# SuperCapV3Control.net
KiCad netlist of a schematic drawn in Altium Designer
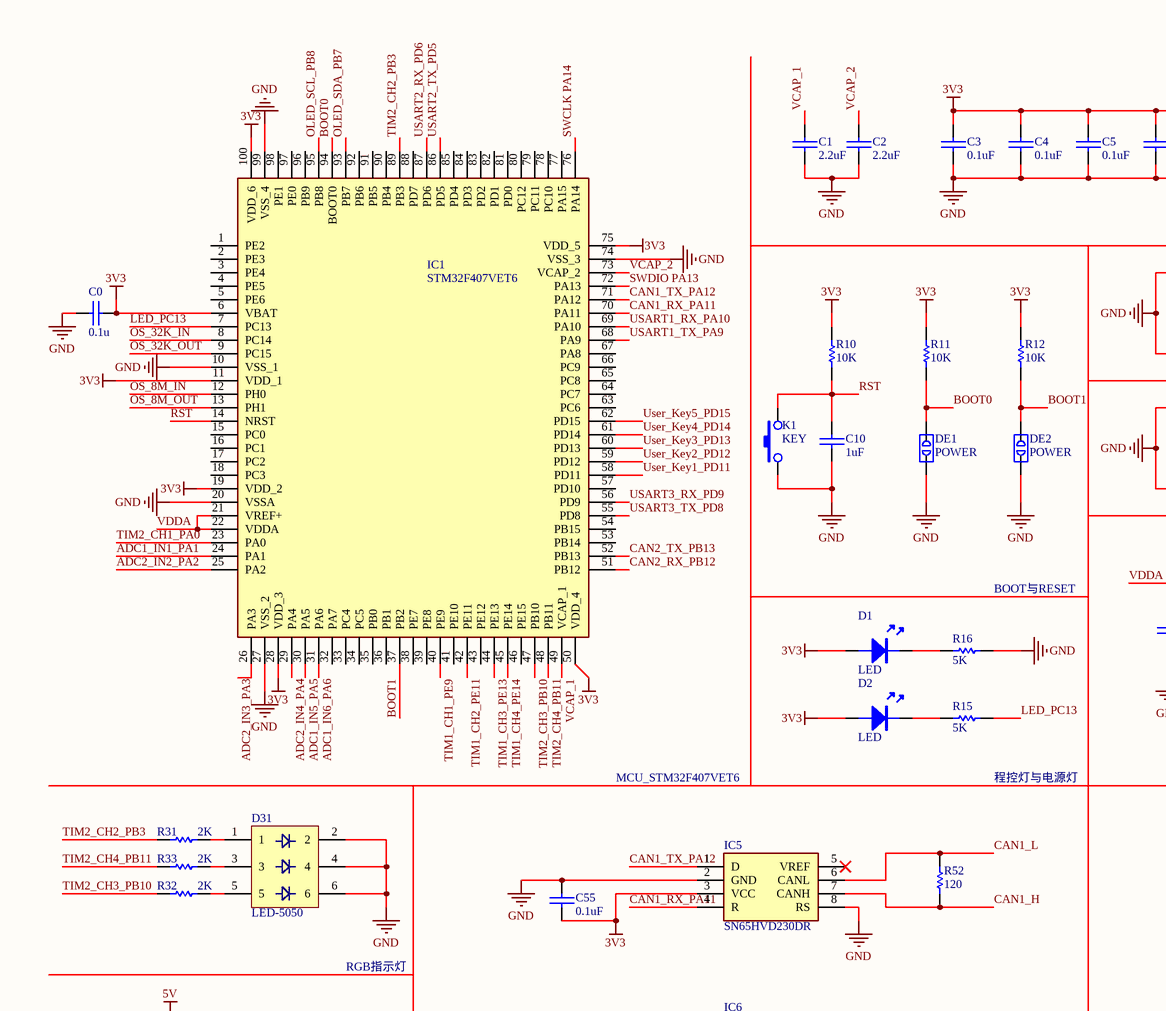
[diagram p0: SuperCapV3Control.SchDoc, top left]
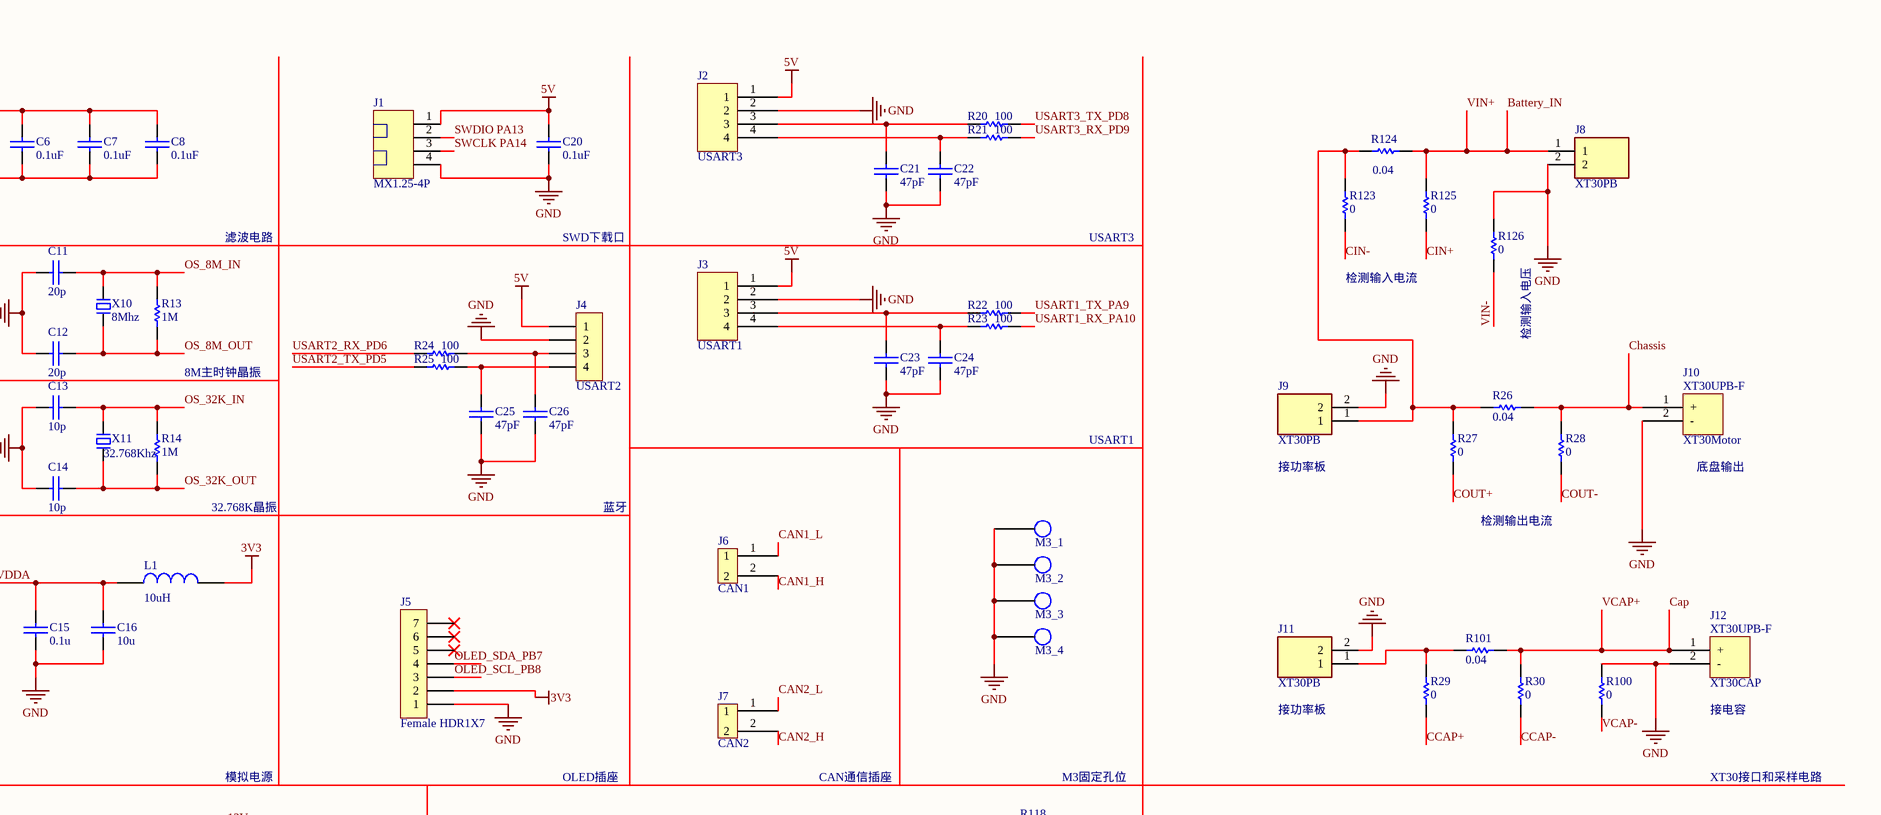
[diagram p1: SuperCapV3Control.SchDoc, top right]
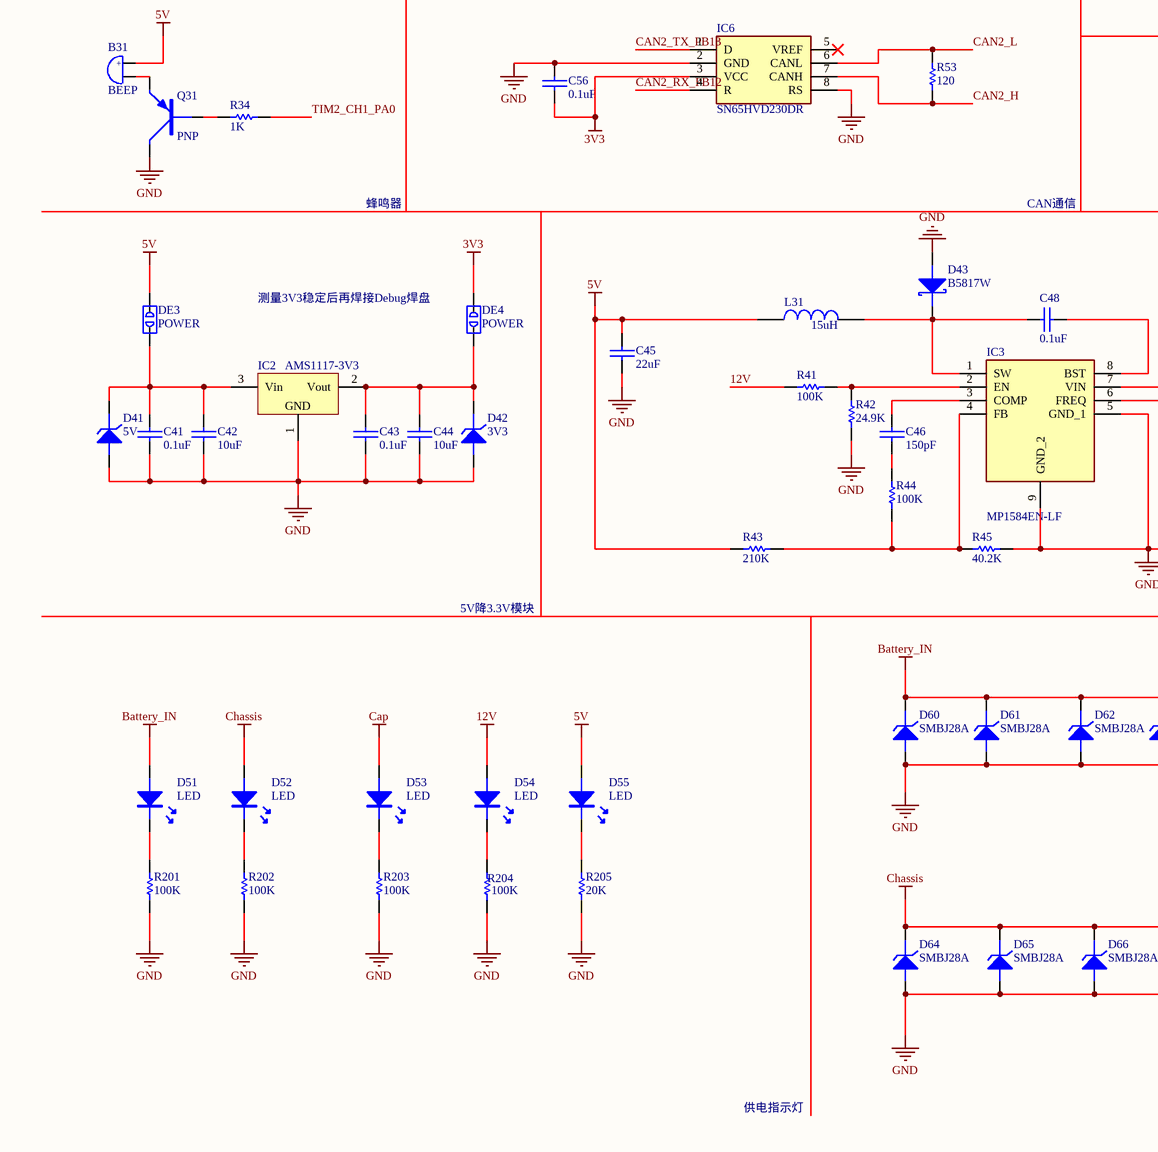
[diagram p2: SuperCapV3Control.SchDoc, bottom left]
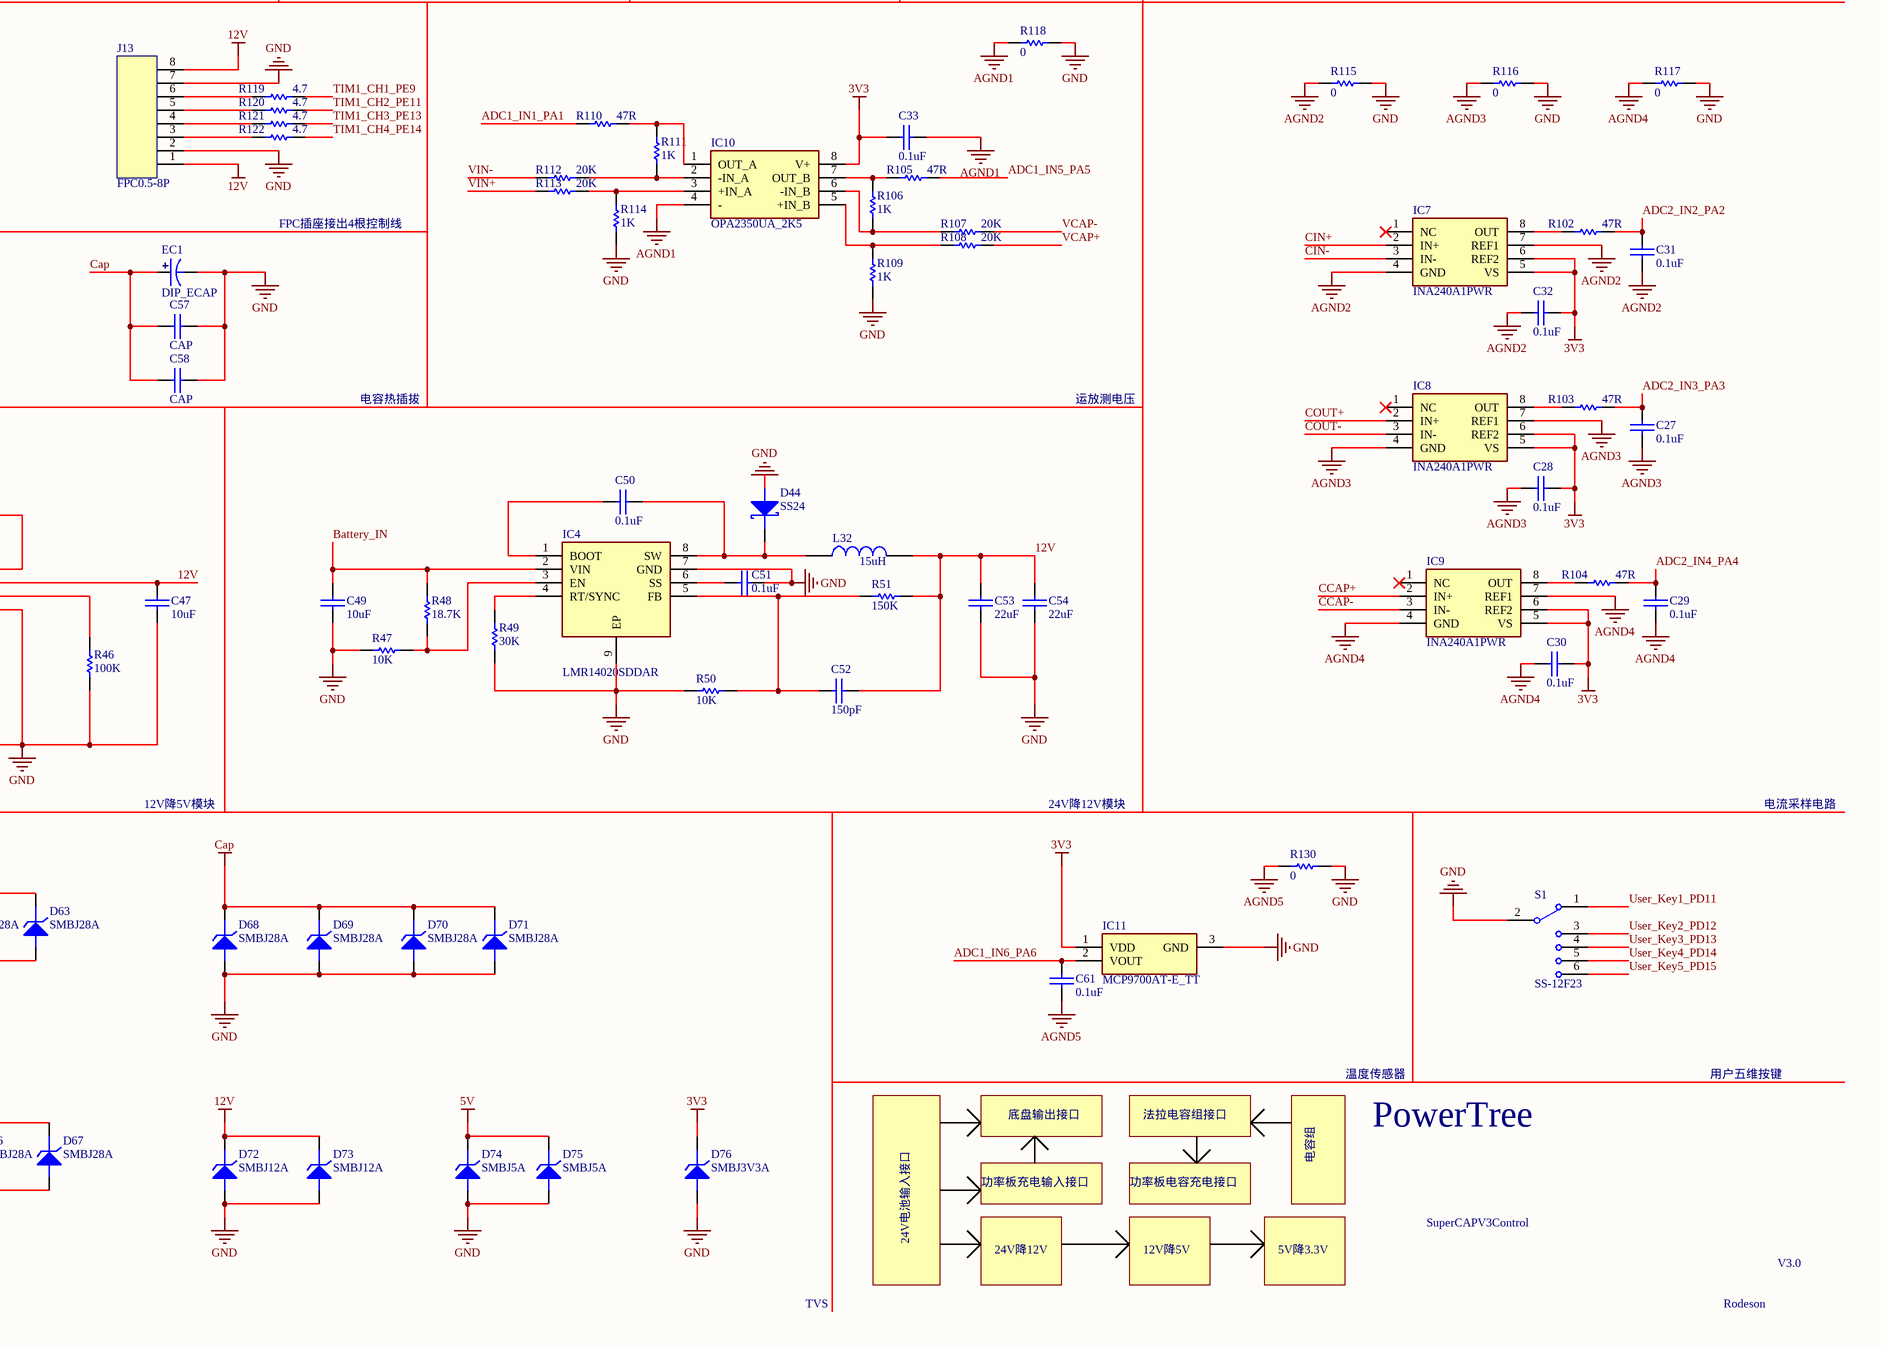
[diagram p3: SuperCapV3Control.SchDoc, bottom right]

(export (version "E")
  (design (tool "Eeschema 10.0.6"))
  (components
    (comp (ref "B31")
      (value "BEEP")
      (footprint "BEEP 6.5x12x8.5")
      (description "蜂鸣器")
      (libsource (lib "蜂鸣器") (part "BEEP"))
    )
    (comp (ref "C0")
      (value "0.1u")
      (footprint "0603C")
      (description "无极性电容")
      (libsource (lib "电容") (part "CAP"))
    )
    (comp (ref "C1")
      (value "2.2uF")
      (footprint "0603C")
      (description "无极性电容")
      (libsource (lib "电容") (part "CAP"))
    )
    (comp (ref "C2")
      (value "2.2uF")
      (footprint "0603C")
      (description "无极性电容")
      (libsource (lib "电容") (part "CAP"))
    )
    (comp (ref "C3")
      (value "0.1uF")
      (footprint "0603C")
      (description "无极性电容")
      (libsource (lib "电容") (part "CAP"))
    )
    (comp (ref "C4")
      (value "0.1uF")
      (footprint "0603C")
      (description "无极性电容")
      (libsource (lib "电容") (part "CAP"))
    )
    (comp (ref "C5")
      (value "0.1uF")
      (footprint "0603C")
      (description "无极性电容")
      (libsource (lib "电容") (part "CAP"))
    )
    (comp (ref "C6")
      (value "0.1uF")
      (footprint "0603C")
      (description "无极性电容")
      (libsource (lib "电容") (part "CAP"))
    )
    (comp (ref "C7")
      (value "0.1uF")
      (footprint "0603C")
      (description "无极性电容")
      (libsource (lib "电容") (part "CAP"))
    )
    (comp (ref "C8")
      (value "0.1uF")
      (footprint "0603C")
      (description "无极性电容")
      (libsource (lib "电容") (part "CAP"))
    )
    (comp (ref "C10")
      (value "1uF")
      (footprint "0603C")
      (description "无极性电容")
      (libsource (lib "电容") (part "CAP"))
    )
    (comp (ref "C11")
      (value "20p")
      (footprint "0603C")
      (description "无极性电容")
      (libsource (lib "电容") (part "CAP"))
    )
    (comp (ref "C12")
      (value "20p")
      (footprint "0603C")
      (description "无极性电容")
      (libsource (lib "电容") (part "CAP"))
    )
    (comp (ref "C13")
      (value "10p")
      (footprint "0603C")
      (description "无极性电容")
      (libsource (lib "电容") (part "CAP"))
    )
    (comp (ref "C14")
      (value "10p")
      (footprint "0603C")
      (description "无极性电容")
      (libsource (lib "电容") (part "CAP"))
    )
    (comp (ref "C15")
      (value "0.1u")
      (footprint "0603C")
      (description "无极性电容")
      (libsource (lib "电容") (part "CAP"))
    )
    (comp (ref "C16")
      (value "10u")
      (footprint "0603C")
      (description "无极性电容")
      (libsource (lib "电容") (part "CAP"))
    )
    (comp (ref "C20")
      (value "0.1uF")
      (footprint "0603C")
      (description "无极性电容")
      (libsource (lib "电容") (part "CAP"))
    )
    (comp (ref "C21")
      (value "47pF")
      (footprint "0603C")
      (description "无极性电容")
      (libsource (lib "电容") (part "CAP"))
    )
    (comp (ref "C22")
      (value "47pF")
      (footprint "0603C")
      (description "无极性电容")
      (libsource (lib "电容") (part "CAP"))
    )
    (comp (ref "C23")
      (value "47pF")
      (footprint "0603C")
      (description "无极性电容")
      (libsource (lib "电容") (part "CAP"))
    )
    (comp (ref "C24")
      (value "47pF")
      (footprint "0603C")
      (description "无极性电容")
      (libsource (lib "电容") (part "CAP"))
    )
    (comp (ref "C25")
      (value "47pF")
      (footprint "0603C")
      (description "无极性电容")
      (libsource (lib "电容") (part "CAP"))
    )
    (comp (ref "C26")
      (value "47pF")
      (footprint "0603C")
      (description "无极性电容")
      (libsource (lib "电容") (part "CAP"))
    )
    (comp (ref "C27")
      (value "0.1uF")
      (footprint "0603C")
      (description "无极性电容")
      (libsource (lib "电容") (part "CAP"))
    )
    (comp (ref "C28")
      (value "0.1uF")
      (footprint "0603C")
      (description "无极性电容")
      (libsource (lib "电容") (part "CAP"))
    )
    (comp (ref "C29")
      (value "0.1uF")
      (footprint "0603C")
      (description "无极性电容")
      (libsource (lib "电容") (part "CAP"))
    )
    (comp (ref "C30")
      (value "0.1uF")
      (footprint "0603C")
      (description "无极性电容")
      (libsource (lib "电容") (part "CAP"))
    )
    (comp (ref "C31")
      (value "0.1uF")
      (footprint "0603C")
      (description "无极性电容")
      (libsource (lib "电容") (part "CAP"))
    )
    (comp (ref "C32")
      (value "0.1uF")
      (footprint "0603C")
      (description "无极性电容")
      (libsource (lib "电容") (part "CAP"))
    )
    (comp (ref "C33")
      (value "0.1uF")
      (footprint "0603C")
      (description "无极性电容")
      (libsource (lib "电容") (part "CAP"))
    )
    (comp (ref "C41")
      (value "0.1uF")
      (footprint "0805C")
      (description "无极性电容")
      (libsource (lib "电容") (part "CAP"))
    )
    (comp (ref "C42")
      (value "10uF")
      (footprint "0805C")
      (description "无极性电容")
      (libsource (lib "电容") (part "CAP"))
    )
    (comp (ref "C43")
      (value "0.1uF")
      (footprint "0805C")
      (description "无极性电容")
      (libsource (lib "电容") (part "CAP"))
    )
    (comp (ref "C44")
      (value "10uF")
      (footprint "0805C")
      (description "无极性电容")
      (libsource (lib "电容") (part "CAP"))
    )
    (comp (ref "C45")
      (value "22uF")
      (footprint "1206C")
      (description "无极性电容")
      (libsource (lib "电容") (part "CAP"))
    )
    (comp (ref "C46")
      (value "150pF")
      (footprint "0603C")
      (description "无极性电容")
      (libsource (lib "电容") (part "CAP"))
    )
    (comp (ref "C47")
      (value "10uF")
      (footprint "1206C")
      (description "无极性电容")
      (libsource (lib "电容") (part "CAP"))
    )
    (comp (ref "C48")
      (value "0.1uF")
      (footprint "0603C")
      (description "无极性电容")
      (libsource (lib "电容") (part "CAP"))
    )
    (comp (ref "C49")
      (value "10uF")
      (footprint "1206C")
      (description "无极性电容")
      (libsource (lib "电容") (part "CAP"))
    )
    (comp (ref "C50")
      (value "0.1uF")
      (footprint "0603C")
      (description "无极性电容")
      (libsource (lib "电容") (part "CAP"))
    )
    (comp (ref "C51")
      (value "0.1uF")
      (footprint "0603C")
      (description "无极性电容")
      (libsource (lib "电容") (part "CAP"))
    )
    (comp (ref "C52")
      (value "150pF")
      (footprint "0603C")
      (description "无极性电容")
      (libsource (lib "电容") (part "CAP"))
    )
    (comp (ref "C53")
      (value "22uF")
      (footprint "1206C")
      (description "无极性电容")
      (libsource (lib "电容") (part "CAP"))
    )
    (comp (ref "C54")
      (value "22uF")
      (footprint "1206C")
      (description "无极性电容")
      (libsource (lib "电容") (part "CAP"))
    )
    (comp (ref "C55")
      (value "0.1uF")
      (footprint "0603C")
      (description "无极性电容")
      (libsource (lib "电容") (part "CAP"))
    )
    (comp (ref "C56")
      (value "0.1uF")
      (footprint "0603C")
      (description "无极性电容")
      (libsource (lib "电容") (part "CAP"))
    )
    (comp (ref "C57")
      (value "CAP")
      (footprint "1812C")
      (description "无极性电容")
      (libsource (lib "电容") (part "CAP"))
    )
    (comp (ref "C58")
      (value "CAP")
      (footprint "1812C")
      (description "无极性电容")
      (libsource (lib "电容") (part "CAP"))
    )
    (comp (ref "C61")
      (value "0.1uF")
      (footprint "0603C")
      (description "无极性电容")
      (libsource (lib "电容") (part "CAP"))
    )
    (comp (ref "D1") (value "LED") (footprint "LED-0603G") (libsource (lib "LED") (part "LED")))
    (comp (ref "D2") (value "LED") (footprint "LED-0603G") (libsource (lib "LED") (part "LED")))
    (comp (ref "D31") (value "LED-5050") (footprint "LED-5050W") (libsource (lib "LED") (part "LED-5050")))
    (comp (ref "D41")
      (value "5V")
      (footprint "SMC/DO-214AB")
      (description "稳压二极管")
      (libsource (lib "二极管") (part "DIODE ZENER"))
    )
    (comp (ref "D42")
      (value "3V3")
      (footprint "SMC/DO-214AB")
      (description "稳压二极管")
      (libsource (lib "二极管") (part "DIODE ZENER"))
    )
    (comp (ref "D43")
      (value "B5817W")
      (footprint "SMA/DO-214AC")
      (description "肖特基二极管")
      (libsource (lib "SuperCap_V2") (part "DIODE SCHOTTKY"))
    )
    (comp (ref "D44")
      (value "SS24")
      (footprint "SMA/DO-214AC")
      (description "肖特基二极管")
      (libsource (lib "SuperCap_V2") (part "DIODE SCHOTTKY"))
    )
    (comp (ref "D51") (value "LED") (footprint "LED-0603G") (libsource (lib "5VDC") (part "LED")))
    (comp (ref "D52") (value "LED") (footprint "LED-0603G") (libsource (lib "5VDC") (part "LED")))
    (comp (ref "D53") (value "LED") (footprint "LED-0603G") (libsource (lib "5VDC") (part "LED")))
    (comp (ref "D54") (value "LED") (footprint "LED-0603G") (libsource (lib "5VDC") (part "LED")))
    (comp (ref "D55") (value "LED") (footprint "LED-0603G") (libsource (lib "5VDC") (part "LED")))
    (comp (ref "D60")
      (value "SMBJ28A")
      (footprint "SMB/DO-214AA")
      (description "稳压二极管")
      (libsource (lib "二极管") (part "DIODE ZENER"))
    )
    (comp (ref "D61")
      (value "SMBJ28A")
      (footprint "SMB/DO-214AA")
      (description "稳压二极管")
      (libsource (lib "二极管") (part "DIODE ZENER"))
    )
    (comp (ref "D62")
      (value "SMBJ28A")
      (footprint "SMB/DO-214AA")
      (description "稳压二极管")
      (libsource (lib "二极管") (part "DIODE ZENER"))
    )
    (comp (ref "D63")
      (value "SMBJ28A")
      (footprint "SMB/DO-214AA")
      (description "稳压二极管")
      (libsource (lib "二极管") (part "DIODE ZENER"))
    )
    (comp (ref "D64")
      (value "SMBJ28A")
      (footprint "SMB/DO-214AA")
      (description "稳压二极管")
      (libsource (lib "二极管") (part "DIODE ZENER"))
    )
    (comp (ref "D65")
      (value "SMBJ28A")
      (footprint "SMB/DO-214AA")
      (description "稳压二极管")
      (libsource (lib "二极管") (part "DIODE ZENER"))
    )
    (comp (ref "D66")
      (value "SMBJ28A")
      (footprint "SMB/DO-214AA")
      (description "稳压二极管")
      (libsource (lib "二极管") (part "DIODE ZENER"))
    )
    (comp (ref "D67")
      (value "SMBJ28A")
      (footprint "SMB/DO-214AA")
      (description "稳压二极管")
      (libsource (lib "二极管") (part "DIODE ZENER"))
    )
    (comp (ref "D68")
      (value "SMBJ28A")
      (footprint "SMB/DO-214AA")
      (description "稳压二极管")
      (libsource (lib "二极管") (part "DIODE ZENER"))
    )
    (comp (ref "D69")
      (value "SMBJ28A")
      (footprint "SMB/DO-214AA")
      (description "稳压二极管")
      (libsource (lib "二极管") (part "DIODE ZENER"))
    )
    (comp (ref "D70")
      (value "SMBJ28A")
      (footprint "SMB/DO-214AA")
      (description "稳压二极管")
      (libsource (lib "二极管") (part "DIODE ZENER"))
    )
    (comp (ref "D71")
      (value "SMBJ28A")
      (footprint "SMB/DO-214AA")
      (description "稳压二极管")
      (libsource (lib "二极管") (part "DIODE ZENER"))
    )
    (comp (ref "D72")
      (value "SMBJ12A")
      (footprint "SMB/DO-214AA")
      (description "稳压二极管")
      (libsource (lib "二极管") (part "DIODE ZENER"))
    )
    (comp (ref "D73")
      (value "SMBJ12A")
      (footprint "SMB/DO-214AA")
      (description "稳压二极管")
      (libsource (lib "二极管") (part "DIODE ZENER"))
    )
    (comp (ref "D74")
      (value "SMBJ5A")
      (footprint "SMB/DO-214AA")
      (description "稳压二极管")
      (libsource (lib "二极管") (part "DIODE ZENER"))
    )
    (comp (ref "D75")
      (value "SMBJ5A")
      (footprint "SMB/DO-214AA")
      (description "稳压二极管")
      (libsource (lib "二极管") (part "DIODE ZENER"))
    )
    (comp (ref "D76")
      (value "SMBJ3V3A")
      (footprint "SMB/DO-214AA")
      (description "稳压二极管")
      (libsource (lib "二极管") (part "DIODE ZENER"))
    )
    (comp (ref "DE1")
      (value "POWER")
      (footprint "DEBUG_A")
      (description "调试断点焊盘")
      (fields (field (name "版权归属") "源创客"))
      (libsource (lib "装甲板第二版") (part "DEBUG"))
    )
    (comp (ref "DE2")
      (value "POWER")
      (footprint "DEBUG_A")
      (description "调试断点焊盘")
      (fields (field (name "版权归属") "源创客"))
      (libsource (lib "装甲板第二版") (part "DEBUG"))
    )
    (comp (ref "DE3")
      (value "POWER")
      (footprint "DEBUG_A")
      (description "调试断点焊盘")
      (fields (field (name "版权归属") "源创客"))
      (libsource (lib "装甲板第二版") (part "DEBUG"))
    )
    (comp (ref "DE4")
      (value "POWER")
      (footprint "DEBUG_A")
      (description "调试断点焊盘")
      (fields (field (name "版权归属") "源创客"))
      (libsource (lib "装甲板第二版") (part "DEBUG"))
    )
    (comp (ref "EC1")
      (value "DIP_ECAP")
      (footprint "DIP-EC5.0X10X20-A")
      (description "直插电解电容")
      (libsource (lib "电容") (part "DIP_ECAP"))
    )
    (comp (ref "IC1")
      (value "STM32F407VET6")
      (footprint "SamacSys:QFP50P1600X1600X160-100N")
      (description "Integrated Circuit")
      (fields (field (name "MOUSER PART NUMBER") "511-STM32F407VET6"))
      (libsource (lib "*") (part "STM32F407VET6"))
    )
    (comp (ref "IC2")
      (value "AMS1117-3V3")
      (footprint "SOT-223")
      (description "三端稳压芯片")
      (fields (field (name "版权归属") "源创客"))
      (libsource (lib "装甲板第二版") (part "AMS1117"))
    )
    (comp (ref "IC3")
      (value "MP1584EN-LF")
      (footprint "SamacSys:SOIC127P600X170-9N")
      (description "Integrated Circuit")
      (fields (field (name "MOUSER PART NUMBER") "946-MP1584ENLF"))
      (libsource (lib "SamacSys") (part "MP1584EN-LF"))
    )
    (comp (ref "IC4")
      (value "LMR14020SDDAR")
      (footprint "SamacSys:SOIC127P600X170-9N")
      (description "Integrated Circuit")
      (fields (field (name "MOUSER PART NUMBER") "595-LMR14020SDDAR"))
      (libsource (lib "*") (part "LMR14020SDDAR"))
    )
    (comp (ref "IC5")
      (value "SN65HVD230DR")
      (footprint "SamacSys:SOT127P600X175-8N")
      (description "Integrated Circuit")
      (fields (field (name "MOUSER PART NUMBER") "595-SN65HVD230DR"))
      (libsource (lib "*") (part "SN65HVD230DR"))
    )
    (comp (ref "IC6")
      (value "SN65HVD230DR")
      (footprint "SamacSys:SOT127P600X175-8N")
      (description "Integrated Circuit")
      (fields (field (name "MOUSER PART NUMBER") "595-SN65HVD230DR"))
      (libsource (lib "*") (part "SN65HVD230DR"))
    )
    (comp (ref "IC7")
      (value "INA240A1PWR")
      (footprint "SamacSys:SOP65P640X120-8N")
      (description "Integrated Circuit")
      (fields (field (name "MOUSER PART NUMBER") "595-INA240A1PWR"))
      (libsource (lib "*") (part "INA240A1PWR"))
    )
    (comp (ref "IC8")
      (value "INA240A1PWR")
      (footprint "SamacSys:SOP65P640X120-8N")
      (description "Integrated Circuit")
      (fields (field (name "MOUSER PART NUMBER") "595-INA240A1PWR"))
      (libsource (lib "*") (part "INA240A1PWR"))
    )
    (comp (ref "IC9")
      (value "INA240A1PWR")
      (footprint "SamacSys:SOP65P640X120-8N")
      (description "Integrated Circuit")
      (fields (field (name "MOUSER PART NUMBER") "595-INA240A1PWR"))
      (libsource (lib "*") (part "INA240A1PWR"))
    )
    (comp (ref "IC10")
      (value "OPA2350UA_2K5")
      (footprint "SamacSys:SOIC127P600X175-8N")
      (description "Integrated Circuit")
      (fields
        (field (name "MANUFACTURER_PART_NUMBER") "OPA2350UA/2K5")
        (field (name "MOUSER PART NUMBER") "595-OPA2350UA/2K5")
      )
      (libsource (lib "*") (part "OPA2350UA_2K5"))
    )
    (comp (ref "IC11")
      (value "MCP9700AT-E_TT")
      (footprint "SOT23")
      (description "Integrated Circuit")
      (fields
        (field (name "MANUFACTURER_PART_NUMBER") "MCP9700AT-E/TT")
        (field (name "MOUSER PART NUMBER") "579-MCP9700AT-E/TT")
      )
      (libsource (lib "*") (part "MCP9700AT-E_TT"))
    )
    (comp (ref "J1") (value "MX1.25-4P") (footprint "MX1.25WS-4P") (libsource (lib "MX") (part "MX1.25-4P")))
    (comp (ref "J2") (value "USART3") (footprint "GH1.25_4P") (libsource (lib "GH1.25") (part "GH1.25_4P")))
    (comp (ref "J3") (value "USART1") (footprint "GH1.25_4P") (libsource (lib "GH1.25") (part "GH1.25_4P")))
    (comp (ref "J4")
      (value "USART2")
      (footprint "Fe-HDR1X4/2.54-S")
      (libsource (lib "排母") (part "Female HDR1X4"))
    )
    (comp (ref "J5")
      (value "Female HDR1X7")
      (footprint "Fe-HDR1X7/2.54-S")
      (libsource (lib "排母") (part "Female HDR1X7"))
    )
    (comp (ref "J6") (value "CAN1") (footprint "GH1.25_2P") (libsource (lib "GH1.25") (part "GH1.25_2P")))
    (comp (ref "J7") (value "CAN2") (footprint "GH1.25_2P") (libsource (lib "GH1.25") (part "GH1.25_2P")))
    (comp (ref "J8")
      (value "XT30PB")
      (footprint "SamacSys:XT30PB")
      (description "Connector")
      (libsource (lib "SamacSys") (part "XT30PB"))
    )
    (comp (ref "J9")
      (value "XT30PB")
      (footprint "SamacSys:XT30PB")
      (description "Connector")
      (libsource (lib "") (part "XT30PB_1"))
    )
    (comp (ref "J10")
      (value "XT30Motor")
      (footprint "XT30UPB-F")
      (libsource (lib "powerdesigner") (part "XT30UPB-F"))
    )
    (comp (ref "J11")
      (value "XT30PB")
      (footprint "SamacSys:XT30PB")
      (description "Connector")
      (libsource (lib "") (part "XT30PB_1"))
    )
    (comp (ref "J12")
      (value "XT30CAP")
      (footprint "XT30UPB-F")
      (libsource (lib "powerdesigner") (part "XT30UPB-F"))
    )
    (comp (ref "J13")
      (value "FPC0.5-8P")
      (footprint "FPC0.5-8P")
      (description "贴片")
      (libsource (lib "FPC") (part "FPC0.5-8P"))
    )
    (comp (ref "K1") (value "KEY") (footprint "SMD-3X6X2.5") (libsource (lib "轻触开关") (part "KEY")))
    (comp (ref "L1")
      (value "10uH")
      (footprint "0603L")
      (description "INDUCTOR")
      (libsource (lib "电感") (part "INDUCTOR"))
    )
    (comp (ref "L31")
      (value "15uH")
      (footprint "0630L")
      (description "INDUCTOR")
      (libsource (lib "电感") (part "INDUCTOR"))
    )
    (comp (ref "L32")
      (value "15uH")
      (footprint "0630L")
      (description "INDUCTOR")
      (libsource (lib "电感") (part "INDUCTOR"))
    )
    (comp (ref "M3_1") (value "Hole") (footprint "M3") (libsource (lib "SuperCap_V2") (part "Hole")))
    (comp (ref "M3_2") (value "Hole") (footprint "M3") (libsource (lib "SuperCap_V2") (part "Hole")))
    (comp (ref "M3_3") (value "Hole") (footprint "M3") (libsource (lib "SuperCap_V2") (part "Hole")))
    (comp (ref "M3_4") (value "Hole") (footprint "M3") (libsource (lib "SuperCap_V2") (part "Hole")))
    (comp (ref "Q31")
      (value "PNP")
      (footprint "SOT-23")
      (description "PNP三极管")
      (libsource (lib "三极管") (part "PNP"))
    )
    (comp (ref "R10") (value "10K") (footprint "0603R") (libsource (lib "电阻") (part "RES")))
    (comp (ref "R11") (value "10K") (footprint "0603R") (libsource (lib "电阻") (part "RES")))
    (comp (ref "R12") (value "10K") (footprint "0603R") (libsource (lib "电阻") (part "RES")))
    (comp (ref "R13") (value "1M") (footprint "0805R") (libsource (lib "电阻") (part "RES")))
    (comp (ref "R14") (value "1M") (footprint "0805R") (libsource (lib "电阻") (part "RES")))
    (comp (ref "R15") (value "5K") (footprint "0603R") (libsource (lib "电阻") (part "RES")))
    (comp (ref "R16") (value "5K") (footprint "0603R") (libsource (lib "电阻") (part "RES")))
    (comp (ref "R20") (value "100") (footprint "0603R") (libsource (lib "电阻") (part "RES")))
    (comp (ref "R21") (value "100") (footprint "0603R") (libsource (lib "电阻") (part "RES")))
    (comp (ref "R22") (value "100") (footprint "0603R") (libsource (lib "电阻") (part "RES")))
    (comp (ref "R23") (value "100") (footprint "0603R") (libsource (lib "电阻") (part "RES")))
    (comp (ref "R24") (value "100") (footprint "0603R") (libsource (lib "电阻") (part "RES")))
    (comp (ref "R25") (value "100") (footprint "0603R") (libsource (lib "电阻") (part "RES")))
    (comp (ref "R26") (value "0.04") (footprint "2512R") (libsource (lib "电阻") (part "RES")))
    (comp (ref "R27") (value "0") (footprint "0603R") (libsource (lib "电阻") (part "RES")))
    (comp (ref "R28") (value "0") (footprint "0603R") (libsource (lib "电阻") (part "RES")))
    (comp (ref "R29") (value "0") (footprint "0603R") (libsource (lib "电阻") (part "RES")))
    (comp (ref "R30") (value "0") (footprint "0603R") (libsource (lib "电阻") (part "RES")))
    (comp (ref "R31") (value "2K") (footprint "0603R") (libsource (lib "电阻") (part "RES")))
    (comp (ref "R32") (value "2K") (footprint "0603R") (libsource (lib "电阻") (part "RES")))
    (comp (ref "R33") (value "2K") (footprint "0603R") (libsource (lib "电阻") (part "RES")))
    (comp (ref "R34") (value "1K") (footprint "0603R") (libsource (lib "电阻") (part "RES")))
    (comp (ref "R41") (value "100K") (footprint "0603R") (libsource (lib "电阻") (part "RES")))
    (comp (ref "R42") (value "24.9K") (footprint "0603R") (libsource (lib "电阻") (part "RES")))
    (comp (ref "R43") (value "210K") (footprint "0603R") (libsource (lib "电阻") (part "RES")))
    (comp (ref "R44") (value "100K") (footprint "0603R") (libsource (lib "电阻") (part "RES")))
    (comp (ref "R45") (value "40.2K") (footprint "0603R") (libsource (lib "电阻") (part "RES")))
    (comp (ref "R46") (value "100K") (footprint "0603R") (libsource (lib "电阻") (part "RES")))
    (comp (ref "R47") (value "10K") (footprint "0603R") (libsource (lib "电阻") (part "RES")))
    (comp (ref "R48") (value "18.7K") (footprint "0603R") (libsource (lib "电阻") (part "RES")))
    (comp (ref "R49") (value "30K") (footprint "0603R") (libsource (lib "电阻") (part "RES")))
    (comp (ref "R50") (value "10K") (footprint "0603R") (libsource (lib "电阻") (part "RES")))
    (comp (ref "R51") (value "150K") (footprint "0603R") (libsource (lib "电阻") (part "RES")))
    (comp (ref "R52") (value "120") (footprint "0603R") (libsource (lib "电阻") (part "RES")))
    (comp (ref "R53") (value "120") (footprint "0603R") (libsource (lib "电阻") (part "RES")))
    (comp (ref "R100") (value "0") (footprint "0603R") (libsource (lib "电阻") (part "RES")))
    (comp (ref "R101") (value "0.04") (footprint "2512R") (libsource (lib "电阻") (part "RES")))
    (comp (ref "R102") (value "47R") (footprint "0805R") (libsource (lib "电阻") (part "RES")))
    (comp (ref "R103") (value "47R") (footprint "0805R") (libsource (lib "电阻") (part "RES")))
    (comp (ref "R104") (value "47R") (footprint "0805R") (libsource (lib "电阻") (part "RES")))
    (comp (ref "R105") (value "47R") (footprint "0603R") (libsource (lib "电阻") (part "RES")))
    (comp (ref "R106") (value "1K") (footprint "0603R") (libsource (lib "电阻") (part "RES")))
    (comp (ref "R107") (value "20K") (footprint "0603R") (libsource (lib "电阻") (part "RES")))
    (comp (ref "R108") (value "20K") (footprint "0603R") (libsource (lib "电阻") (part "RES")))
    (comp (ref "R109") (value "1K") (footprint "0603R") (libsource (lib "电阻") (part "RES")))
    (comp (ref "R110") (value "47R") (footprint "0603R") (libsource (lib "电阻") (part "RES")))
    (comp (ref "R111") (value "1K") (footprint "0603R") (libsource (lib "电阻") (part "RES")))
    (comp (ref "R112") (value "20K") (footprint "0603R") (libsource (lib "电阻") (part "RES")))
    (comp (ref "R113") (value "20K") (footprint "0603R") (libsource (lib "电阻") (part "RES")))
    (comp (ref "R114") (value "1K") (footprint "0603R") (libsource (lib "电阻") (part "RES")))
    (comp (ref "R115") (value "0") (footprint "0603R") (libsource (lib "电阻") (part "RES")))
    (comp (ref "R116") (value "0") (footprint "0603R") (libsource (lib "电阻") (part "RES")))
    (comp (ref "R117") (value "0") (footprint "0603R") (libsource (lib "电阻") (part "RES")))
    (comp (ref "R118") (value "0") (footprint "0603R") (libsource (lib "电阻") (part "RES")))
    (comp (ref "R119") (value "4.7") (footprint "0603R") (libsource (lib "电阻") (part "RES")))
    (comp (ref "R120") (value "4.7") (footprint "0603R") (libsource (lib "电阻") (part "RES")))
    (comp (ref "R121") (value "4.7") (footprint "0603R") (libsource (lib "电阻") (part "RES")))
    (comp (ref "R122") (value "4.7") (footprint "0603R") (libsource (lib "电阻") (part "RES")))
    (comp (ref "R123") (value "0") (footprint "0603R") (libsource (lib "电阻") (part "RES")))
    (comp (ref "R124") (value "0.04") (footprint "2512R") (libsource (lib "电阻") (part "RES")))
    (comp (ref "R125") (value "0") (footprint "0603R") (libsource (lib "电阻") (part "RES")))
    (comp (ref "R126") (value "0") (footprint "0603R") (libsource (lib "电阻") (part "RES")))
    (comp (ref "R130") (value "0") (footprint "0603R") (libsource (lib "电阻") (part "RES")))
    (comp (ref "R201") (value "100K") (footprint "0603R") (libsource (lib "电阻") (part "RES")))
    (comp (ref "R202") (value "100K") (footprint "0603R") (libsource (lib "电阻") (part "RES")))
    (comp (ref "R203") (value "100K") (footprint "0603R") (libsource (lib "电阻") (part "RES")))
    (comp (ref "R204") (value "100K") (footprint "0603R") (libsource (lib "电阻") (part "RES")))
    (comp (ref "R205") (value "20K") (footprint "0603R") (libsource (lib "电阻") (part "RES")))
    (comp (ref "S1")
      (value "SS-12F23")
      (footprint "五向开关")
      (description "五向开关")
      (fields (field (name "版权归属") "源创客"))
      (libsource (lib "试做1型") (part "SSW-1P"))
    )
    (comp (ref "X10")
      (value "8Mhz")
      (footprint "OSC HC-49S")
      (description "2脚无源脚晶振")
      (libsource (lib "晶振") (part "XTAL-2P"))
    )
    (comp (ref "X11")
      (value "32.768Khz")
      (footprint "OSC HC-49S")
      (description "2脚无源脚晶振")
      (libsource (lib "晶振") (part "XTAL-2P"))
    )
  )
  (nets
    (net (code "1") (name "/ADC1_IN1_PA1") (class "Default")
      (node (ref "IC1") (pin "24") (pinfunction "PA1_24") (pintype "passive"))
      (node (ref "R110") (pin "1") (pinfunction "1_1") (pintype "passive"))
    )
    (net (code "2") (name "/ADC1_IN5_PA5") (class "Default")
      (node (ref "IC1") (pin "30") (pinfunction "PA5_30") (pintype "passive"))
      (node (ref "R105") (pin "2") (pinfunction "2_2") (pintype "passive"))
    )
    (net (code "3") (name "/ADC1_IN6_PA6") (class "Default")
      (node (ref "C61") (pin "2") (pinfunction "2_2") (pintype "passive"))
      (node (ref "IC1") (pin "31") (pinfunction "PA6_31") (pintype "passive"))
      (node (ref "IC11") (pin "2") (pinfunction "VOUT_2") (pintype "passive"))
    )
    (net (code "4") (name "/ADC2_IN2_PA2") (class "Default")
      (node (ref "C31") (pin "1") (pinfunction "1_1") (pintype "passive"))
      (node (ref "IC1") (pin "25") (pinfunction "PA2_25") (pintype "passive"))
      (node (ref "R102") (pin "2") (pinfunction "2_2") (pintype "passive"))
    )
    (net (code "5") (name "/ADC2_IN3_PA3") (class "Default")
      (node (ref "C27") (pin "1") (pinfunction "1_1") (pintype "passive"))
      (node (ref "IC1") (pin "26") (pinfunction "PA3_26") (pintype "passive"))
      (node (ref "R103") (pin "2") (pinfunction "2_2") (pintype "passive"))
    )
    (net (code "6") (name "/ADC2_IN4_PA4") (class "Default")
      (node (ref "C29") (pin "1") (pinfunction "1_1") (pintype "passive"))
      (node (ref "IC1") (pin "29") (pinfunction "PA4_29") (pintype "passive"))
      (node (ref "R104") (pin "2") (pinfunction "2_2") (pintype "passive"))
    )
    (net (code "7") (name "/BOOT0") (class "Default")
      (node (ref "DE1") (pin "2") (pinfunction "2_2") (pintype "passive"))
      (node (ref "IC1") (pin "94") (pinfunction "BOOT0_94") (pintype "passive"))
      (node (ref "R11") (pin "1") (pinfunction "1_1") (pintype "passive"))
    )
    (net (code "8") (name "/BOOT1") (class "Default")
      (node (ref "DE2") (pin "2") (pinfunction "2_2") (pintype "passive"))
      (node (ref "IC1") (pin "37") (pinfunction "PB2_37") (pintype "passive"))
      (node (ref "R12") (pin "1") (pinfunction "1_1") (pintype "passive"))
    )
    (net (code "9") (name "/CAN1_H") (class "Default")
      (node (ref "IC5") (pin "7") (pinfunction "CANH_7") (pintype "passive"))
      (node (ref "J6") (pin "2") (pinfunction "2_2") (pintype "passive"))
      (node (ref "R52") (pin "1") (pinfunction "1_1") (pintype "passive"))
    )
    (net (code "10") (name "/CAN1_L") (class "Default")
      (node (ref "IC5") (pin "6") (pinfunction "CANL_6") (pintype "passive"))
      (node (ref "J6") (pin "1") (pinfunction "1_1") (pintype "passive"))
      (node (ref "R52") (pin "2") (pinfunction "2_2") (pintype "passive"))
    )
    (net (code "11") (name "/CAN1_RX_PA11") (class "Default")
      (node (ref "IC1") (pin "70") (pinfunction "PA11_70") (pintype "passive"))
      (node (ref "IC5") (pin "4") (pinfunction "R_4") (pintype "passive"))
    )
    (net (code "12") (name "/CAN1_TX_PA12") (class "Default")
      (node (ref "IC1") (pin "71") (pinfunction "PA12_71") (pintype "passive"))
      (node (ref "IC5") (pin "1") (pinfunction "D_1") (pintype "passive"))
    )
    (net (code "13") (name "/CAN2_H") (class "Default")
      (node (ref "IC6") (pin "7") (pinfunction "CANH_7") (pintype "passive"))
      (node (ref "J7") (pin "2") (pinfunction "2_2") (pintype "passive"))
      (node (ref "R53") (pin "1") (pinfunction "1_1") (pintype "passive"))
    )
    (net (code "14") (name "/CAN2_L") (class "Default")
      (node (ref "IC6") (pin "6") (pinfunction "CANL_6") (pintype "passive"))
      (node (ref "J7") (pin "1") (pinfunction "1_1") (pintype "passive"))
      (node (ref "R53") (pin "2") (pinfunction "2_2") (pintype "passive"))
    )
    (net (code "15") (name "/CAN2_RX_PB12") (class "Default")
      (node (ref "IC1") (pin "51") (pinfunction "PB12_51") (pintype "passive"))
      (node (ref "IC6") (pin "4") (pinfunction "R_4") (pintype "passive"))
    )
    (net (code "16") (name "/CAN2_TX_PB13") (class "Default")
      (node (ref "IC1") (pin "52") (pinfunction "PB13_52") (pintype "passive"))
      (node (ref "IC6") (pin "1") (pinfunction "D_1") (pintype "passive"))
    )
    (net (code "17") (name "/CCAP+") (class "Default")
      (node (ref "IC9") (pin "2") (pinfunction "IN+_2") (pintype "passive"))
      (node (ref "R29") (pin "1") (pinfunction "1_1") (pintype "passive"))
    )
    (net (code "18") (name "/CCAP-") (class "Default")
      (node (ref "IC9") (pin "3") (pinfunction "IN-_3") (pintype "passive"))
      (node (ref "R30") (pin "1") (pinfunction "1_1") (pintype "passive"))
    )
    (net (code "19") (name "/CIN+") (class "Default")
      (node (ref "IC7") (pin "2") (pinfunction "IN+_2") (pintype "passive"))
      (node (ref "R125") (pin "1") (pinfunction "1_1") (pintype "passive"))
    )
    (net (code "20") (name "/CIN-") (class "Default")
      (node (ref "IC7") (pin "3") (pinfunction "IN-_3") (pintype "passive"))
      (node (ref "R123") (pin "1") (pinfunction "1_1") (pintype "passive"))
    )
    (net (code "21") (name "/COUT+") (class "Default")
      (node (ref "IC8") (pin "2") (pinfunction "IN+_2") (pintype "passive"))
      (node (ref "R27") (pin "1") (pinfunction "1_1") (pintype "passive"))
    )
    (net (code "22") (name "/COUT-") (class "Default")
      (node (ref "IC8") (pin "3") (pinfunction "IN-_3") (pintype "passive"))
      (node (ref "R28") (pin "1") (pinfunction "1_1") (pintype "passive"))
    )
    (net (code "23") (name "/LED_PC13") (class "Default")
      (node (ref "IC1") (pin "7") (pinfunction "PC13_7") (pintype "passive"))
      (node (ref "R15") (pin "2") (pinfunction "2_2") (pintype "passive"))
    )
    (net (code "24") (name "/OLED_SCL_PB8") (class "Default")
      (node (ref "IC1") (pin "95") (pinfunction "PB8_95") (pintype "passive"))
      (node (ref "J5") (pin "3") (pinfunction "3_3") (pintype "passive"))
    )
    (net (code "25") (name "/OLED_SDA_PB7") (class "Default")
      (node (ref "IC1") (pin "93") (pinfunction "PB7_93") (pintype "passive"))
      (node (ref "J5") (pin "4") (pinfunction "4_4") (pintype "passive"))
    )
    (net (code "26") (name "/OS_8M_IN") (class "Default")
      (node (ref "C11") (pin "2") (pinfunction "2_2") (pintype "passive"))
      (node (ref "IC1") (pin "12") (pinfunction "PH0_12") (pintype "passive"))
      (node (ref "R13") (pin "2") (pinfunction "2_2") (pintype "passive"))
      (node (ref "X10") (pin "2") (pinfunction "2_2") (pintype "passive"))
    )
    (net (code "27") (name "/OS_8M_OUT") (class "Default")
      (node (ref "C12") (pin "2") (pinfunction "2_2") (pintype "passive"))
      (node (ref "IC1") (pin "13") (pinfunction "PH1_13") (pintype "passive"))
      (node (ref "R13") (pin "1") (pinfunction "1_1") (pintype "passive"))
      (node (ref "X10") (pin "1") (pinfunction "1_1") (pintype "passive"))
    )
    (net (code "28") (name "/OS_32K_IN") (class "Default")
      (node (ref "C13") (pin "2") (pinfunction "2_2") (pintype "passive"))
      (node (ref "IC1") (pin "8") (pinfunction "PC14_8") (pintype "passive"))
      (node (ref "R14") (pin "2") (pinfunction "2_2") (pintype "passive"))
      (node (ref "X11") (pin "2") (pinfunction "2_2") (pintype "passive"))
    )
    (net (code "29") (name "/OS_32K_OUT") (class "Default")
      (node (ref "C14") (pin "2") (pinfunction "2_2") (pintype "passive"))
      (node (ref "IC1") (pin "9") (pinfunction "PC15_9") (pintype "passive"))
      (node (ref "R14") (pin "1") (pinfunction "1_1") (pintype "passive"))
      (node (ref "X11") (pin "1") (pinfunction "1_1") (pintype "passive"))
    )
    (net (code "30") (name "/RST") (class "Default")
      (node (ref "C10") (pin "2") (pinfunction "2_2") (pintype "passive"))
      (node (ref "IC1") (pin "14") (pinfunction "NRST_14") (pintype "passive"))
      (node (ref "K1") (pin "3") (pinfunction "3_3") (pintype "passive"))
      (node (ref "R10") (pin "1") (pinfunction "1_1") (pintype "passive"))
    )
    (net (code "31") (name "/SWCLK PA14") (class "Default")
      (node (ref "IC1") (pin "76") (pinfunction "PA14_76") (pintype "passive"))
      (node (ref "J1") (pin "3") (pinfunction "3_3") (pintype "passive"))
    )
    (net (code "32") (name "/SWDIO PA13") (class "Default")
      (node (ref "IC1") (pin "72") (pinfunction "PA13_72") (pintype "passive"))
      (node (ref "J1") (pin "2") (pinfunction "2_2") (pintype "passive"))
    )
    (net (code "33") (name "/TIM1_CH1_PE9") (class "Default")
      (node (ref "IC1") (pin "40") (pinfunction "PE9_40") (pintype "passive"))
      (node (ref "R119") (pin "2") (pinfunction "2_2") (pintype "passive"))
    )
    (net (code "34") (name "/TIM1_CH2_PE11") (class "Default")
      (node (ref "IC1") (pin "42") (pinfunction "PE11_42") (pintype "passive"))
      (node (ref "R120") (pin "2") (pinfunction "2_2") (pintype "passive"))
    )
    (net (code "35") (name "/TIM1_CH3_PE13") (class "Default")
      (node (ref "IC1") (pin "44") (pinfunction "PE13_44") (pintype "passive"))
      (node (ref "R121") (pin "2") (pinfunction "2_2") (pintype "passive"))
    )
    (net (code "36") (name "/TIM1_CH4_PE14") (class "Default")
      (node (ref "IC1") (pin "45") (pinfunction "PE14_45") (pintype "passive"))
      (node (ref "R122") (pin "2") (pinfunction "2_2") (pintype "passive"))
    )
    (net (code "37") (name "/TIM2_CH1_PA0") (class "Default")
      (node (ref "IC1") (pin "23") (pinfunction "PA0_23") (pintype "passive"))
      (node (ref "R34") (pin "2") (pinfunction "2_2") (pintype "passive"))
    )
    (net (code "38") (name "/TIM2_CH2_PB3") (class "Default")
      (node (ref "IC1") (pin "89") (pinfunction "PB3_89") (pintype "passive"))
      (node (ref "R31") (pin "1") (pinfunction "1_1") (pintype "passive"))
    )
    (net (code "39") (name "/TIM2_CH3_PB10") (class "Default")
      (node (ref "IC1") (pin "47") (pinfunction "PB10_47") (pintype "passive"))
      (node (ref "R32") (pin "1") (pinfunction "1_1") (pintype "passive"))
    )
    (net (code "40") (name "/TIM2_CH4_PB11") (class "Default")
      (node (ref "IC1") (pin "48") (pinfunction "PB11_48") (pintype "passive"))
      (node (ref "R33") (pin "1") (pinfunction "1_1") (pintype "passive"))
    )
    (net (code "41") (name "/USART1_RX_PA10") (class "Default")
      (node (ref "IC1") (pin "69") (pinfunction "PA10_69") (pintype "passive"))
      (node (ref "R23") (pin "2") (pinfunction "2_2") (pintype "passive"))
    )
    (net (code "42") (name "/USART1_TX_PA9") (class "Default")
      (node (ref "IC1") (pin "68") (pinfunction "PA9_68") (pintype "passive"))
      (node (ref "R22") (pin "2") (pinfunction "2_2") (pintype "passive"))
    )
    (net (code "43") (name "/USART2_RX_PD6") (class "Default")
      (node (ref "IC1") (pin "87") (pinfunction "PD6_87") (pintype "passive"))
      (node (ref "R24") (pin "1") (pinfunction "1_1") (pintype "passive"))
    )
    (net (code "44") (name "/USART2_TX_PD5") (class "Default")
      (node (ref "IC1") (pin "86") (pinfunction "PD5_86") (pintype "passive"))
      (node (ref "R25") (pin "1") (pinfunction "1_1") (pintype "passive"))
    )
    (net (code "45") (name "/USART3_RX_PD9") (class "Default")
      (node (ref "IC1") (pin "56") (pinfunction "PD9_56") (pintype "passive"))
      (node (ref "R21") (pin "2") (pinfunction "2_2") (pintype "passive"))
    )
    (net (code "46") (name "/USART3_TX_PD8") (class "Default")
      (node (ref "IC1") (pin "55") (pinfunction "PD8_55") (pintype "passive"))
      (node (ref "R20") (pin "2") (pinfunction "2_2") (pintype "passive"))
    )
    (net (code "47") (name "/User_Key1_PD11") (class "Default")
      (node (ref "IC1") (pin "58") (pinfunction "PD11_58") (pintype "passive"))
      (node (ref "S1") (pin "1") (pinfunction "1_1") (pintype "passive"))
    )
    (net (code "48") (name "/User_Key2_PD12") (class "Default")
      (node (ref "IC1") (pin "59") (pinfunction "PD12_59") (pintype "passive"))
      (node (ref "S1") (pin "3") (pinfunction "3_3") (pintype "passive"))
    )
    (net (code "49") (name "/User_Key3_PD13") (class "Default")
      (node (ref "IC1") (pin "60") (pinfunction "PD13_60") (pintype "passive"))
      (node (ref "S1") (pin "4") (pinfunction "4_4") (pintype "passive"))
    )
    (net (code "50") (name "/User_Key4_PD14") (class "Default")
      (node (ref "IC1") (pin "61") (pinfunction "PD14_61") (pintype "passive"))
      (node (ref "S1") (pin "5") (pinfunction "5_5") (pintype "passive"))
    )
    (net (code "51") (name "/User_Key5_PD15") (class "Default")
      (node (ref "IC1") (pin "62") (pinfunction "PD15_62") (pintype "passive"))
      (node (ref "S1") (pin "6") (pinfunction "6_6") (pintype "passive"))
    )
    (net (code "52") (name "/VCAP-") (class "Default")
      (node (ref "R100") (pin "1") (pinfunction "1_1") (pintype "passive"))
      (node (ref "R107") (pin "2") (pinfunction "2_2") (pintype "passive"))
    )
    (net (code "53") (name "/VCAP_1") (class "Default")
      (node (ref "C1") (pin "2") (pinfunction "2_2") (pintype "passive"))
      (node (ref "IC1") (pin "49") (pinfunction "VCAP_1_49") (pintype "passive"))
    )
    (net (code "54") (name "/VCAP_2") (class "Default")
      (node (ref "C2") (pin "2") (pinfunction "2_2") (pintype "passive"))
      (node (ref "IC1") (pin "73") (pinfunction "VCAP_2_73") (pintype "passive"))
    )
    (net (code "55") (name "/VDDA") (class "Default")
      (node (ref "C15") (pin "2") (pinfunction "2_2") (pintype "passive"))
      (node (ref "C16") (pin "2") (pinfunction "2_2") (pintype "passive"))
      (node (ref "IC1") (pin "21") (pinfunction "VREF+_21") (pintype "passive"))
      (node (ref "IC1") (pin "22") (pinfunction "VDDA_22") (pintype "passive"))
      (node (ref "L1") (pin "1") (pinfunction "1_1") (pintype "passive"))
    )
    (net (code "56") (name "/VIN-") (class "Default")
      (node (ref "R112") (pin "1") (pinfunction "1_1") (pintype "passive"))
      (node (ref "R126") (pin "1") (pinfunction "1_1") (pintype "passive"))
    )
    (net (code "57") (name "3V3") (class "Default")
      (node (ref "C0") (pin "1") (pinfunction "1_1") (pintype "passive"))
      (node (ref "C28") (pin "2") (pinfunction "2_2") (pintype "passive"))
      (node (ref "C3") (pin "2") (pinfunction "2_2") (pintype "passive"))
      (node (ref "C30") (pin "2") (pinfunction "2_2") (pintype "passive"))
      (node (ref "C32") (pin "2") (pinfunction "2_2") (pintype "passive"))
      (node (ref "C33") (pin "1") (pinfunction "1_1") (pintype "passive"))
      (node (ref "C4") (pin "2") (pinfunction "2_2") (pintype "passive"))
      (node (ref "C5") (pin "2") (pinfunction "2_2") (pintype "passive"))
      (node (ref "C55") (pin "1") (pinfunction "1_1") (pintype "passive"))
      (node (ref "C56") (pin "1") (pinfunction "1_1") (pintype "passive"))
      (node (ref "C6") (pin "2") (pinfunction "2_2") (pintype "passive"))
      (node (ref "C7") (pin "2") (pinfunction "2_2") (pintype "passive"))
      (node (ref "C8") (pin "2") (pinfunction "2_2") (pintype "passive"))
      (node (ref "D1") (pin "A") (pinfunction "A_A") (pintype "passive"))
      (node (ref "D2") (pin "A") (pinfunction "A_A") (pintype "passive"))
      (node (ref "D76") (pin "K") (pinfunction "K_K") (pintype "passive"))
      (node (ref "DE4") (pin "1") (pinfunction "1_1") (pintype "passive"))
      (node (ref "IC1") (pin "100") (pinfunction "VDD_6_100") (pintype "passive"))
      (node (ref "IC1") (pin "11") (pinfunction "VDD_1_11") (pintype "passive"))
      (node (ref "IC1") (pin "19") (pinfunction "VDD_2_19") (pintype "passive"))
      (node (ref "IC1") (pin "28") (pinfunction "VDD_3_28") (pintype "passive"))
      (node (ref "IC1") (pin "50") (pinfunction "VDD_4_50") (pintype "passive"))
      (node (ref "IC1") (pin "6") (pinfunction "VBAT_6") (pintype "passive"))
      (node (ref "IC1") (pin "75") (pinfunction "VDD_5_75") (pintype "passive"))
      (node (ref "IC10") (pin "8") (pinfunction "V+_8") (pintype "passive"))
      (node (ref "IC11") (pin "1") (pinfunction "VDD_1") (pintype "passive"))
      (node (ref "IC5") (pin "3") (pinfunction "VCC_3") (pintype "passive"))
      (node (ref "IC6") (pin "3") (pinfunction "VCC_3") (pintype "passive"))
      (node (ref "IC7") (pin "5") (pinfunction "VS_5") (pintype "passive"))
      (node (ref "IC7") (pin "6") (pinfunction "REF2_6") (pintype "passive"))
      (node (ref "IC8") (pin "5") (pinfunction "VS_5") (pintype "passive"))
      (node (ref "IC8") (pin "6") (pinfunction "REF2_6") (pintype "passive"))
      (node (ref "IC9") (pin "5") (pinfunction "VS_5") (pintype "passive"))
      (node (ref "IC9") (pin "6") (pinfunction "REF2_6") (pintype "passive"))
      (node (ref "J5") (pin "2") (pinfunction "2_2") (pintype "passive"))
      (node (ref "L1") (pin "2") (pinfunction "2_2") (pintype "passive"))
      (node (ref "R10") (pin "2") (pinfunction "2_2") (pintype "passive"))
      (node (ref "R11") (pin "2") (pinfunction "2_2") (pintype "passive"))
      (node (ref "R12") (pin "2") (pinfunction "2_2") (pintype "passive"))
    )
    (net (code "58") (name "5V") (class "Default")
      (node (ref "B31") (pin "1") (pinfunction "1_1") (pintype "passive"))
      (node (ref "C20") (pin "2") (pinfunction "2_2") (pintype "passive"))
      (node (ref "C45") (pin "2") (pinfunction "2_2") (pintype "passive"))
      (node (ref "D55") (pin "A") (pinfunction "A_A") (pintype "passive"))
      (node (ref "D74") (pin "K") (pinfunction "K_K") (pintype "passive"))
      (node (ref "D75") (pin "K") (pinfunction "K_K") (pintype "passive"))
      (node (ref "DE3") (pin "1") (pinfunction "1_1") (pintype "passive"))
      (node (ref "J1") (pin "1") (pinfunction "1_1") (pintype "passive"))
      (node (ref "J2") (pin "1") (pinfunction "1_1") (pintype "passive"))
      (node (ref "J3") (pin "1") (pinfunction "1_1") (pintype "passive"))
      (node (ref "J4") (pin "1") (pinfunction "1_1") (pintype "passive"))
      (node (ref "L31") (pin "1") (pinfunction "1_1") (pintype "passive"))
      (node (ref "R43") (pin "1") (pinfunction "1_1") (pintype "passive"))
    )
    (net (code "59") (name "12V") (class "Default")
      (node (ref "C47") (pin "2") (pinfunction "2_2") (pintype "passive"))
      (node (ref "C52") (pin "2") (pinfunction "2_2") (pintype "passive"))
      (node (ref "C53") (pin "2") (pinfunction "2_2") (pintype "passive"))
      (node (ref "C54") (pin "2") (pinfunction "2_2") (pintype "passive"))
      (node (ref "D54") (pin "A") (pinfunction "A_A") (pintype "passive"))
      (node (ref "D72") (pin "K") (pinfunction "K_K") (pintype "passive"))
      (node (ref "D73") (pin "K") (pinfunction "K_K") (pintype "passive"))
      (node (ref "IC3") (pin "7") (pinfunction "VIN_7") (pintype "passive"))
      (node (ref "J13") (pin "1") (pinfunction "1_1") (pintype "passive"))
      (node (ref "J13") (pin "8") (pinfunction "8_8") (pintype "passive"))
      (node (ref "L32") (pin "2") (pinfunction "2_2") (pintype "passive"))
      (node (ref "R41") (pin "1") (pinfunction "1_1") (pintype "passive"))
      (node (ref "R51") (pin "2") (pinfunction "2_2") (pintype "passive"))
    )
    (net (code "60") (name "AGND1") (class "Default")
      (node (ref "C33") (pin "2") (pinfunction "2_2") (pintype "passive"))
      (node (ref "IC10") (pin "4") (pinfunction "-_4") (pintype "passive"))
      (node (ref "R118") (pin "2") (pinfunction "2_2") (pintype "passive"))
    )
    (net (code "61") (name "AGND2") (class "Default")
      (node (ref "C31") (pin "2") (pinfunction "2_2") (pintype "passive"))
      (node (ref "C32") (pin "1") (pinfunction "1_1") (pintype "passive"))
      (node (ref "IC7") (pin "4") (pinfunction "GND_4") (pintype "passive"))
      (node (ref "IC7") (pin "7") (pinfunction "REF1_7") (pintype "passive"))
      (node (ref "R115") (pin "2") (pinfunction "2_2") (pintype "passive"))
    )
    (net (code "62") (name "AGND3") (class "Default")
      (node (ref "C27") (pin "2") (pinfunction "2_2") (pintype "passive"))
      (node (ref "C28") (pin "1") (pinfunction "1_1") (pintype "passive"))
      (node (ref "IC8") (pin "4") (pinfunction "GND_4") (pintype "passive"))
      (node (ref "IC8") (pin "7") (pinfunction "REF1_7") (pintype "passive"))
      (node (ref "R116") (pin "2") (pinfunction "2_2") (pintype "passive"))
    )
    (net (code "63") (name "AGND4") (class "Default")
      (node (ref "C29") (pin "2") (pinfunction "2_2") (pintype "passive"))
      (node (ref "C30") (pin "1") (pinfunction "1_1") (pintype "passive"))
      (node (ref "IC9") (pin "4") (pinfunction "GND_4") (pintype "passive"))
      (node (ref "IC9") (pin "7") (pinfunction "REF1_7") (pintype "passive"))
      (node (ref "R117") (pin "2") (pinfunction "2_2") (pintype "passive"))
    )
    (net (code "64") (name "AGND5") (class "Default")
      (node (ref "C61") (pin "1") (pinfunction "1_1") (pintype "passive"))
      (node (ref "R130") (pin "2") (pinfunction "2_2") (pintype "passive"))
    )
    (net (code "65") (name "Battery_IN") (class "Default")
      (node (ref "C49") (pin "2") (pinfunction "2_2") (pintype "passive"))
      (node (ref "D51") (pin "A") (pinfunction "A_A") (pintype "passive"))
      (node (ref "D60") (pin "K") (pinfunction "K_K") (pintype "passive"))
      (node (ref "D61") (pin "K") (pinfunction "K_K") (pintype "passive"))
      (node (ref "D62") (pin "K") (pinfunction "K_K") (pintype "passive"))
      (node (ref "D63") (pin "K") (pinfunction "K_K") (pintype "passive"))
      (node (ref "IC4") (pin "2") (pinfunction "VIN_2") (pintype "passive"))
      (node (ref "J8") (pin "1") (pinfunction "1_1") (pintype "passive"))
      (node (ref "R113") (pin "1") (pinfunction "1_1") (pintype "passive"))
      (node (ref "R124") (pin "2") (pinfunction "2_2") (pintype "passive"))
      (node (ref "R125") (pin "2") (pinfunction "2_2") (pintype "passive"))
      (node (ref "R48") (pin "1") (pinfunction "1_1") (pintype "passive"))
    )
    (net (code "66") (name "Cap") (class "Default")
      (node (ref "C57") (pin "1") (pinfunction "1_1") (pintype "passive"))
      (node (ref "C58") (pin "1") (pinfunction "1_1") (pintype "passive"))
      (node (ref "D53") (pin "A") (pinfunction "A_A") (pintype "passive"))
      (node (ref "D68") (pin "K") (pinfunction "K_K") (pintype "passive"))
      (node (ref "D69") (pin "K") (pinfunction "K_K") (pintype "passive"))
      (node (ref "D70") (pin "K") (pinfunction "K_K") (pintype "passive"))
      (node (ref "D71") (pin "K") (pinfunction "K_K") (pintype "passive"))
      (node (ref "EC1") (pin "1") (pinfunction "1_1") (pintype "passive"))
      (node (ref "J12") (pin "1") (pinfunction "+_1") (pintype "passive"))
      (node (ref "R101") (pin "2") (pinfunction "2_2") (pintype "passive"))
      (node (ref "R108") (pin "2") (pinfunction "2_2") (pintype "passive"))
      (node (ref "R30") (pin "2") (pinfunction "2_2") (pintype "passive"))
    )
    (net (code "67") (name "Chassis") (class "Default")
      (node (ref "D52") (pin "A") (pinfunction "A_A") (pintype "passive"))
      (node (ref "D64") (pin "K") (pinfunction "K_K") (pintype "passive"))
      (node (ref "D65") (pin "K") (pinfunction "K_K") (pintype "passive"))
      (node (ref "D66") (pin "K") (pinfunction "K_K") (pintype "passive"))
      (node (ref "D67") (pin "K") (pinfunction "K_K") (pintype "passive"))
      (node (ref "J10") (pin "1") (pinfunction "+_1") (pintype "passive"))
      (node (ref "R26") (pin "2") (pinfunction "2_2") (pintype "passive"))
      (node (ref "R28") (pin "2") (pinfunction "2_2") (pintype "passive"))
    )
    (net (code "68") (name "GND") (class "Default")
      (node (ref "C0") (pin "2") (pinfunction "2_2") (pintype "passive"))
      (node (ref "C1") (pin "1") (pinfunction "1_1") (pintype "passive"))
      (node (ref "C10") (pin "1") (pinfunction "1_1") (pintype "passive"))
      (node (ref "C11") (pin "1") (pinfunction "1_1") (pintype "passive"))
      (node (ref "C12") (pin "1") (pinfunction "1_1") (pintype "passive"))
      (node (ref "C13") (pin "1") (pinfunction "1_1") (pintype "passive"))
      (node (ref "C14") (pin "1") (pinfunction "1_1") (pintype "passive"))
      (node (ref "C15") (pin "1") (pinfunction "1_1") (pintype "passive"))
      (node (ref "C16") (pin "1") (pinfunction "1_1") (pintype "passive"))
      (node (ref "C2") (pin "1") (pinfunction "1_1") (pintype "passive"))
      (node (ref "C20") (pin "1") (pinfunction "1_1") (pintype "passive"))
      (node (ref "C21") (pin "1") (pinfunction "1_1") (pintype "passive"))
      (node (ref "C22") (pin "1") (pinfunction "1_1") (pintype "passive"))
      (node (ref "C23") (pin "1") (pinfunction "1_1") (pintype "passive"))
      (node (ref "C24") (pin "1") (pinfunction "1_1") (pintype "passive"))
      (node (ref "C25") (pin "1") (pinfunction "1_1") (pintype "passive"))
      (node (ref "C26") (pin "1") (pinfunction "1_1") (pintype "passive"))
      (node (ref "C3") (pin "1") (pinfunction "1_1") (pintype "passive"))
      (node (ref "C4") (pin "1") (pinfunction "1_1") (pintype "passive"))
      (node (ref "C41") (pin "1") (pinfunction "1_1") (pintype "passive"))
      (node (ref "C42") (pin "1") (pinfunction "1_1") (pintype "passive"))
      (node (ref "C43") (pin "1") (pinfunction "1_1") (pintype "passive"))
      (node (ref "C44") (pin "1") (pinfunction "1_1") (pintype "passive"))
      (node (ref "C45") (pin "1") (pinfunction "1_1") (pintype "passive"))
      (node (ref "C47") (pin "1") (pinfunction "1_1") (pintype "passive"))
      (node (ref "C49") (pin "1") (pinfunction "1_1") (pintype "passive"))
      (node (ref "C5") (pin "1") (pinfunction "1_1") (pintype "passive"))
      (node (ref "C51") (pin "2") (pinfunction "2_2") (pintype "passive"))
      (node (ref "C53") (pin "1") (pinfunction "1_1") (pintype "passive"))
      (node (ref "C54") (pin "1") (pinfunction "1_1") (pintype "passive"))
      (node (ref "C55") (pin "2") (pinfunction "2_2") (pintype "passive"))
      (node (ref "C56") (pin "2") (pinfunction "2_2") (pintype "passive"))
      (node (ref "C57") (pin "2") (pinfunction "2_2") (pintype "passive"))
      (node (ref "C58") (pin "2") (pinfunction "2_2") (pintype "passive"))
      (node (ref "C6") (pin "1") (pinfunction "1_1") (pintype "passive"))
      (node (ref "C7") (pin "1") (pinfunction "1_1") (pintype "passive"))
      (node (ref "C8") (pin "1") (pinfunction "1_1") (pintype "passive"))
      (node (ref "D31") (pin "2") (pinfunction "2_2") (pintype "passive"))
      (node (ref "D31") (pin "4") (pinfunction "4_4") (pintype "passive"))
      (node (ref "D31") (pin "6") (pinfunction "6_6") (pintype "passive"))
      (node (ref "D41") (pin "A") (pinfunction "A_A") (pintype "passive"))
      (node (ref "D42") (pin "A") (pinfunction "A_A") (pintype "passive"))
      (node (ref "D43") (pin "A") (pinfunction "A_A") (pintype "passive"))
      (node (ref "D44") (pin "A") (pinfunction "A_A") (pintype "passive"))
      (node (ref "D60") (pin "A") (pinfunction "A_A") (pintype "passive"))
      (node (ref "D61") (pin "A") (pinfunction "A_A") (pintype "passive"))
      (node (ref "D62") (pin "A") (pinfunction "A_A") (pintype "passive"))
      (node (ref "D63") (pin "A") (pinfunction "A_A") (pintype "passive"))
      (node (ref "D64") (pin "A") (pinfunction "A_A") (pintype "passive"))
      (node (ref "D65") (pin "A") (pinfunction "A_A") (pintype "passive"))
      (node (ref "D66") (pin "A") (pinfunction "A_A") (pintype "passive"))
      (node (ref "D67") (pin "A") (pinfunction "A_A") (pintype "passive"))
      (node (ref "D68") (pin "A") (pinfunction "A_A") (pintype "passive"))
      (node (ref "D69") (pin "A") (pinfunction "A_A") (pintype "passive"))
      (node (ref "D70") (pin "A") (pinfunction "A_A") (pintype "passive"))
      (node (ref "D71") (pin "A") (pinfunction "A_A") (pintype "passive"))
      (node (ref "D72") (pin "A") (pinfunction "A_A") (pintype "passive"))
      (node (ref "D73") (pin "A") (pinfunction "A_A") (pintype "passive"))
      (node (ref "D74") (pin "A") (pinfunction "A_A") (pintype "passive"))
      (node (ref "D75") (pin "A") (pinfunction "A_A") (pintype "passive"))
      (node (ref "D76") (pin "A") (pinfunction "A_A") (pintype "passive"))
      (node (ref "DE1") (pin "1") (pinfunction "1_1") (pintype "passive"))
      (node (ref "DE2") (pin "1") (pinfunction "1_1") (pintype "passive"))
      (node (ref "EC1") (pin "2") (pinfunction "2_2") (pintype "passive"))
      (node (ref "IC1") (pin "10") (pinfunction "VSS_1_10") (pintype "passive"))
      (node (ref "IC1") (pin "20") (pinfunction "VSSA_20") (pintype "passive"))
      (node (ref "IC1") (pin "27") (pinfunction "VSS_2_27") (pintype "passive"))
      (node (ref "IC1") (pin "74") (pinfunction "VSS_3_74") (pintype "passive"))
      (node (ref "IC1") (pin "99") (pinfunction "VSS_4_99") (pintype "passive"))
      (node (ref "IC11") (pin "3") (pinfunction "GND_3") (pintype "passive"))
      (node (ref "IC2") (pin "1") (pinfunction "GND_1") (pintype "passive"))
      (node (ref "IC3") (pin "5") (pinfunction "GND_1_5") (pintype "passive"))
      (node (ref "IC3") (pin "9") (pinfunction "GND_2_9") (pintype "passive"))
      (node (ref "IC4") (pin "7") (pinfunction "GND_7") (pintype "passive"))
      (node (ref "IC4") (pin "9") (pinfunction "EP_9") (pintype "passive"))
      (node (ref "IC5") (pin "2") (pinfunction "GND_2") (pintype "passive"))
      (node (ref "IC5") (pin "8") (pinfunction "RS_8") (pintype "passive"))
      (node (ref "IC6") (pin "2") (pinfunction "GND_2") (pintype "passive"))
      (node (ref "IC6") (pin "8") (pinfunction "RS_8") (pintype "passive"))
      (node (ref "J1") (pin "4") (pinfunction "4_4") (pintype "passive"))
      (node (ref "J10") (pin "2") (pinfunction "-_2") (pintype "passive"))
      (node (ref "J11") (pin "2") (pinfunction "2_2") (pintype "passive"))
      (node (ref "J12") (pin "2") (pinfunction "-_2") (pintype "passive"))
      (node (ref "J13") (pin "2") (pinfunction "2_2") (pintype "passive"))
      (node (ref "J13") (pin "7") (pinfunction "7_7") (pintype "passive"))
      (node (ref "J2") (pin "2") (pinfunction "2_2") (pintype "passive"))
      (node (ref "J3") (pin "2") (pinfunction "2_2") (pintype "passive"))
      (node (ref "J4") (pin "2") (pinfunction "2_2") (pintype "passive"))
      (node (ref "J5") (pin "1") (pinfunction "1_1") (pintype "passive"))
      (node (ref "J8") (pin "2") (pinfunction "2_2") (pintype "passive"))
      (node (ref "J9") (pin "2") (pinfunction "2_2") (pintype "passive"))
      (node (ref "K1") (pin "1") (pinfunction "1_1") (pintype "passive"))
      (node (ref "M3_1") (pin "1") (pinfunction "1_1") (pintype "passive"))
      (node (ref "M3_2") (pin "1") (pinfunction "1_1") (pintype "passive"))
      (node (ref "M3_3") (pin "1") (pinfunction "1_1") (pintype "passive"))
      (node (ref "M3_4") (pin "1") (pinfunction "1_1") (pintype "passive"))
      (node (ref "Q31") (pin "C") (pinfunction "C_C") (pintype "passive"))
      (node (ref "R100") (pin "2") (pinfunction "2_2") (pintype "passive"))
      (node (ref "R109") (pin "1") (pinfunction "1_1") (pintype "passive"))
      (node (ref "R114") (pin "1") (pinfunction "1_1") (pintype "passive"))
      (node (ref "R115") (pin "1") (pinfunction "1_1") (pintype "passive"))
      (node (ref "R116") (pin "1") (pinfunction "1_1") (pintype "passive"))
      (node (ref "R117") (pin "1") (pinfunction "1_1") (pintype "passive"))
      (node (ref "R118") (pin "1") (pinfunction "1_1") (pintype "passive"))
      (node (ref "R126") (pin "2") (pinfunction "2_2") (pintype "passive"))
      (node (ref "R130") (pin "1") (pinfunction "1_1") (pintype "passive"))
      (node (ref "R16") (pin "2") (pinfunction "2_2") (pintype "passive"))
      (node (ref "R201") (pin "1") (pinfunction "1_1") (pintype "passive"))
      (node (ref "R202") (pin "1") (pinfunction "1_1") (pintype "passive"))
      (node (ref "R203") (pin "1") (pinfunction "1_1") (pintype "passive"))
      (node (ref "R204") (pin "1") (pinfunction "1_1") (pintype "passive"))
      (node (ref "R205") (pin "1") (pinfunction "1_1") (pintype "passive"))
      (node (ref "R42") (pin "1") (pinfunction "1_1") (pintype "passive"))
      (node (ref "R45") (pin "2") (pinfunction "2_2") (pintype "passive"))
      (node (ref "R46") (pin "1") (pinfunction "1_1") (pintype "passive"))
      (node (ref "R47") (pin "1") (pinfunction "1_1") (pintype "passive"))
      (node (ref "R49") (pin "1") (pinfunction "1_1") (pintype "passive"))
      (node (ref "R50") (pin "1") (pinfunction "1_1") (pintype "passive"))
      (node (ref "S1") (pin "2") (pinfunction "2_2") (pintype "passive"))
    )
    (net (code "69") (name "Net-(B31-Pad2)") (class "Default")
      (node (ref "B31") (pin "2") (pinfunction "2_2") (pintype "passive"))
      (node (ref "Q31") (pin "E") (pinfunction "E_E") (pintype "passive"))
    )
    (net (code "70") (name "Net-(C21-Pad2)") (class "Default")
      (node (ref "C21") (pin "2") (pinfunction "2_2") (pintype "passive"))
      (node (ref "J2") (pin "3") (pinfunction "3_3") (pintype "passive"))
      (node (ref "R20") (pin "1") (pinfunction "1_1") (pintype "passive"))
    )
    (net (code "71") (name "Net-(C22-Pad2)") (class "Default")
      (node (ref "C22") (pin "2") (pinfunction "2_2") (pintype "passive"))
      (node (ref "J2") (pin "4") (pinfunction "4_4") (pintype "passive"))
      (node (ref "R21") (pin "1") (pinfunction "1_1") (pintype "passive"))
    )
    (net (code "72") (name "Net-(C23-Pad2)") (class "Default")
      (node (ref "C23") (pin "2") (pinfunction "2_2") (pintype "passive"))
      (node (ref "J3") (pin "3") (pinfunction "3_3") (pintype "passive"))
      (node (ref "R22") (pin "1") (pinfunction "1_1") (pintype "passive"))
    )
    (net (code "73") (name "Net-(C24-Pad2)") (class "Default")
      (node (ref "C24") (pin "2") (pinfunction "2_2") (pintype "passive"))
      (node (ref "J3") (pin "4") (pinfunction "4_4") (pintype "passive"))
      (node (ref "R23") (pin "1") (pinfunction "1_1") (pintype "passive"))
    )
    (net (code "74") (name "Net-(C25-Pad2)") (class "Default")
      (node (ref "C25") (pin "2") (pinfunction "2_2") (pintype "passive"))
      (node (ref "J4") (pin "4") (pinfunction "4_4") (pintype "passive"))
      (node (ref "R25") (pin "2") (pinfunction "2_2") (pintype "passive"))
    )
    (net (code "75") (name "Net-(C26-Pad2)") (class "Default")
      (node (ref "C26") (pin "2") (pinfunction "2_2") (pintype "passive"))
      (node (ref "J4") (pin "3") (pinfunction "3_3") (pintype "passive"))
      (node (ref "R24") (pin "2") (pinfunction "2_2") (pintype "passive"))
    )
    (net (code "76") (name "Net-(C46-Pad1)") (class "Default")
      (node (ref "C46") (pin "1") (pinfunction "1_1") (pintype "passive"))
      (node (ref "R44") (pin "2") (pinfunction "2_2") (pintype "passive"))
    )
    (net (code "77") (name "Net-(D1-PadK)") (class "Default")
      (node (ref "D1") (pin "K") (pinfunction "K_K") (pintype "passive"))
      (node (ref "R16") (pin "1") (pinfunction "1_1") (pintype "passive"))
    )
    (net (code "78") (name "Net-(D2-PadK)") (class "Default")
      (node (ref "D2") (pin "K") (pinfunction "K_K") (pintype "passive"))
      (node (ref "R15") (pin "1") (pinfunction "1_1") (pintype "passive"))
    )
    (net (code "79") (name "Net-(D31-Pad1)") (class "Default")
      (node (ref "D31") (pin "1") (pinfunction "1_1") (pintype "passive"))
      (node (ref "R31") (pin "2") (pinfunction "2_2") (pintype "passive"))
    )
    (net (code "80") (name "Net-(D31-Pad3)") (class "Default")
      (node (ref "D31") (pin "3") (pinfunction "3_3") (pintype "passive"))
      (node (ref "R33") (pin "2") (pinfunction "2_2") (pintype "passive"))
    )
    (net (code "81") (name "Net-(D31-Pad5)") (class "Default")
      (node (ref "D31") (pin "5") (pinfunction "5_5") (pintype "passive"))
      (node (ref "R32") (pin "2") (pinfunction "2_2") (pintype "passive"))
    )
    (net (code "82") (name "Net-(D51-PadK)") (class "Default")
      (node (ref "D51") (pin "K") (pinfunction "K_K") (pintype "passive"))
      (node (ref "R201") (pin "2") (pinfunction "2_2") (pintype "passive"))
    )
    (net (code "83") (name "Net-(D52-PadK)") (class "Default")
      (node (ref "D52") (pin "K") (pinfunction "K_K") (pintype "passive"))
      (node (ref "R202") (pin "2") (pinfunction "2_2") (pintype "passive"))
    )
    (net (code "84") (name "Net-(D53-PadK)") (class "Default")
      (node (ref "D53") (pin "K") (pinfunction "K_K") (pintype "passive"))
      (node (ref "R203") (pin "2") (pinfunction "2_2") (pintype "passive"))
    )
    (net (code "85") (name "Net-(D54-PadK)") (class "Default")
      (node (ref "D54") (pin "K") (pinfunction "K_K") (pintype "passive"))
      (node (ref "R204") (pin "2") (pinfunction "2_2") (pintype "passive"))
    )
    (net (code "86") (name "Net-(D55-PadK)") (class "Default")
      (node (ref "D55") (pin "K") (pinfunction "K_K") (pintype "passive"))
      (node (ref "R205") (pin "2") (pinfunction "2_2") (pintype "passive"))
    )
    (net (code "87") (name "Net-(IC2-Vin)") (class "Default")
      (node (ref "C41") (pin "2") (pinfunction "2_2") (pintype "passive"))
      (node (ref "C42") (pin "2") (pinfunction "2_2") (pintype "passive"))
      (node (ref "D41") (pin "K") (pinfunction "K_K") (pintype "passive"))
      (node (ref "DE3") (pin "2") (pinfunction "2_2") (pintype "passive"))
      (node (ref "IC2") (pin "3") (pinfunction "Vin_3") (pintype "passive"))
    )
    (net (code "88") (name "Net-(IC2-Vout)") (class "Default")
      (node (ref "C43") (pin "2") (pinfunction "2_2") (pintype "passive"))
      (node (ref "C44") (pin "2") (pinfunction "2_2") (pintype "passive"))
      (node (ref "D42") (pin "K") (pinfunction "K_K") (pintype "passive"))
      (node (ref "DE4") (pin "2") (pinfunction "2_2") (pintype "passive"))
      (node (ref "IC2") (pin "2") (pinfunction "Vout_2") (pintype "passive"))
    )
    (net (code "89") (name "Net-(IC3-BST)") (class "Default")
      (node (ref "C48") (pin "2") (pinfunction "2_2") (pintype "passive"))
      (node (ref "IC3") (pin "8") (pinfunction "BST_8") (pintype "passive"))
    )
    (net (code "90") (name "Net-(IC3-COMP)") (class "Default")
      (node (ref "C46") (pin "2") (pinfunction "2_2") (pintype "passive"))
      (node (ref "IC3") (pin "3") (pinfunction "COMP_3") (pintype "passive"))
    )
    (net (code "91") (name "Net-(IC3-EN)") (class "Default")
      (node (ref "IC3") (pin "2") (pinfunction "EN_2") (pintype "passive"))
      (node (ref "R41") (pin "2") (pinfunction "2_2") (pintype "passive"))
      (node (ref "R42") (pin "2") (pinfunction "2_2") (pintype "passive"))
    )
    (net (code "92") (name "Net-(IC3-FB)") (class "Default")
      (node (ref "IC3") (pin "4") (pinfunction "FB_4") (pintype "passive"))
      (node (ref "R43") (pin "2") (pinfunction "2_2") (pintype "passive"))
      (node (ref "R44") (pin "1") (pinfunction "1_1") (pintype "passive"))
      (node (ref "R45") (pin "1") (pinfunction "1_1") (pintype "passive"))
    )
    (net (code "93") (name "Net-(IC3-FREQ)") (class "Default")
      (node (ref "IC3") (pin "6") (pinfunction "FREQ_6") (pintype "passive"))
      (node (ref "R46") (pin "2") (pinfunction "2_2") (pintype "passive"))
    )
    (net (code "94") (name "Net-(IC3-SW)") (class "Default")
      (node (ref "C48") (pin "1") (pinfunction "1_1") (pintype "passive"))
      (node (ref "D43") (pin "K") (pinfunction "K_K") (pintype "passive"))
      (node (ref "IC3") (pin "1") (pinfunction "SW_1") (pintype "passive"))
      (node (ref "L31") (pin "2") (pinfunction "2_2") (pintype "passive"))
    )
    (net (code "95") (name "Net-(IC4-BOOT)") (class "Default")
      (node (ref "C50") (pin "1") (pinfunction "1_1") (pintype "passive"))
      (node (ref "IC4") (pin "1") (pinfunction "BOOT_1") (pintype "passive"))
    )
    (net (code "96") (name "Net-(IC4-EN)") (class "Default")
      (node (ref "IC4") (pin "3") (pinfunction "EN_3") (pintype "passive"))
      (node (ref "R47") (pin "2") (pinfunction "2_2") (pintype "passive"))
      (node (ref "R48") (pin "2") (pinfunction "2_2") (pintype "passive"))
    )
    (net (code "97") (name "Net-(IC4-FB)") (class "Default")
      (node (ref "C52") (pin "1") (pinfunction "1_1") (pintype "passive"))
      (node (ref "IC4") (pin "5") (pinfunction "FB_5") (pintype "passive"))
      (node (ref "R50") (pin "2") (pinfunction "2_2") (pintype "passive"))
      (node (ref "R51") (pin "1") (pinfunction "1_1") (pintype "passive"))
    )
    (net (code "98") (name "Net-(IC4-RT{slash}SYNC)") (class "Default")
      (node (ref "IC4") (pin "4") (pinfunction "RT/SYNC_4") (pintype "passive"))
      (node (ref "R49") (pin "2") (pinfunction "2_2") (pintype "passive"))
    )
    (net (code "99") (name "Net-(IC4-SS)") (class "Default")
      (node (ref "C51") (pin "1") (pinfunction "1_1") (pintype "passive"))
      (node (ref "IC4") (pin "6") (pinfunction "SS_6") (pintype "passive"))
    )
    (net (code "100") (name "Net-(IC4-SW)") (class "Default")
      (node (ref "C50") (pin "2") (pinfunction "2_2") (pintype "passive"))
      (node (ref "D44") (pin "K") (pinfunction "K_K") (pintype "passive"))
      (node (ref "IC4") (pin "8") (pinfunction "SW_8") (pintype "passive"))
      (node (ref "L32") (pin "1") (pinfunction "1_1") (pintype "passive"))
    )
    (net (code "101") (name "Net-(IC7-OUT)") (class "Default")
      (node (ref "IC7") (pin "8") (pinfunction "OUT_8") (pintype "passive"))
      (node (ref "R102") (pin "1") (pinfunction "1_1") (pintype "passive"))
    )
    (net (code "102") (name "Net-(IC8-OUT)") (class "Default")
      (node (ref "IC8") (pin "8") (pinfunction "OUT_8") (pintype "passive"))
      (node (ref "R103") (pin "1") (pinfunction "1_1") (pintype "passive"))
    )
    (net (code "103") (name "Net-(IC9-OUT)") (class "Default")
      (node (ref "IC9") (pin "8") (pinfunction "OUT_8") (pintype "passive"))
      (node (ref "R104") (pin "1") (pinfunction "1_1") (pintype "passive"))
    )
    (net (code "104") (name "Net-(IC10-+IN_A)") (class "Default")
      (node (ref "IC10") (pin "3") (pinfunction "+IN_A_3") (pintype "passive"))
      (node (ref "R113") (pin "2") (pinfunction "2_2") (pintype "passive"))
      (node (ref "R114") (pin "2") (pinfunction "2_2") (pintype "passive"))
    )
    (net (code "105") (name "Net-(IC10-+IN_B)") (class "Default")
      (node (ref "IC10") (pin "5") (pinfunction "+IN_B_5") (pintype "passive"))
      (node (ref "R108") (pin "1") (pinfunction "1_1") (pintype "passive"))
      (node (ref "R109") (pin "2") (pinfunction "2_2") (pintype "passive"))
    )
    (net (code "106") (name "Net-(IC10--IN_A)") (class "Default")
      (node (ref "IC10") (pin "2") (pinfunction "-IN_A_2") (pintype "passive"))
      (node (ref "R111") (pin "1") (pinfunction "1_1") (pintype "passive"))
      (node (ref "R112") (pin "2") (pinfunction "2_2") (pintype "passive"))
    )
    (net (code "107") (name "Net-(IC10--IN_B)") (class "Default")
      (node (ref "IC10") (pin "6") (pinfunction "-IN_B_6") (pintype "passive"))
      (node (ref "R106") (pin "1") (pinfunction "1_1") (pintype "passive"))
      (node (ref "R107") (pin "1") (pinfunction "1_1") (pintype "passive"))
    )
    (net (code "108") (name "Net-(IC10-OUT_A)") (class "Default")
      (node (ref "IC10") (pin "1") (pinfunction "OUT_A_1") (pintype "passive"))
      (node (ref "R110") (pin "2") (pinfunction "2_2") (pintype "passive"))
      (node (ref "R111") (pin "2") (pinfunction "2_2") (pintype "passive"))
    )
    (net (code "109") (name "Net-(IC10-OUT_B)") (class "Default")
      (node (ref "IC10") (pin "7") (pinfunction "OUT_B_7") (pintype "passive"))
      (node (ref "R105") (pin "1") (pinfunction "1_1") (pintype "passive"))
      (node (ref "R106") (pin "2") (pinfunction "2_2") (pintype "passive"))
    )
    (net (code "110") (name "Net-(J9-Pad1)") (class "Default")
      (node (ref "J9") (pin "1") (pinfunction "1_1") (pintype "passive"))
      (node (ref "R123") (pin "2") (pinfunction "2_2") (pintype "passive"))
      (node (ref "R124") (pin "1") (pinfunction "1_1") (pintype "passive"))
      (node (ref "R26") (pin "1") (pinfunction "1_1") (pintype "passive"))
      (node (ref "R27") (pin "2") (pinfunction "2_2") (pintype "passive"))
    )
    (net (code "111") (name "Net-(J11-Pad1)") (class "Default")
      (node (ref "J11") (pin "1") (pinfunction "1_1") (pintype "passive"))
      (node (ref "R101") (pin "1") (pinfunction "1_1") (pintype "passive"))
      (node (ref "R29") (pin "2") (pinfunction "2_2") (pintype "passive"))
    )
    (net (code "112") (name "Net-(J13-Pad3)") (class "Default")
      (node (ref "J13") (pin "3") (pinfunction "3_3") (pintype "passive"))
      (node (ref "R122") (pin "1") (pinfunction "1_1") (pintype "passive"))
    )
    (net (code "113") (name "Net-(J13-Pad4)") (class "Default")
      (node (ref "J13") (pin "4") (pinfunction "4_4") (pintype "passive"))
      (node (ref "R121") (pin "1") (pinfunction "1_1") (pintype "passive"))
    )
    (net (code "114") (name "Net-(J13-Pad5)") (class "Default")
      (node (ref "J13") (pin "5") (pinfunction "5_5") (pintype "passive"))
      (node (ref "R120") (pin "1") (pinfunction "1_1") (pintype "passive"))
    )
    (net (code "115") (name "Net-(J13-Pad6)") (class "Default")
      (node (ref "J13") (pin "6") (pinfunction "6_6") (pintype "passive"))
      (node (ref "R119") (pin "1") (pinfunction "1_1") (pintype "passive"))
    )
    (net (code "116") (name "Net-(Q31-PadB)") (class "Default")
      (node (ref "Q31") (pin "B") (pinfunction "B_B") (pintype "passive"))
      (node (ref "R34") (pin "1") (pinfunction "1_1") (pintype "passive"))
    )
    (net (code "117") (name "unconnected-(IC1-PA7-Pad32)") (class "Default")
      (node (ref "IC1") (pin "32") (pinfunction "PA7_32") (pintype "passive"))
    )
    (net (code "118") (name "unconnected-(IC1-PA8-Pad67)") (class "Default")
      (node (ref "IC1") (pin "67") (pinfunction "PA8_67") (pintype "passive"))
    )
    (net (code "119") (name "unconnected-(IC1-PA15-Pad77)") (class "Default")
      (node (ref "IC1") (pin "77") (pinfunction "PA15_77") (pintype "passive"))
    )
    (net (code "120") (name "unconnected-(IC1-PB0-Pad35)") (class "Default")
      (node (ref "IC1") (pin "35") (pinfunction "PB0_35") (pintype "passive"))
    )
    (net (code "121") (name "unconnected-(IC1-PB1-Pad36)") (class "Default")
      (node (ref "IC1") (pin "36") (pinfunction "PB1_36") (pintype "passive"))
    )
    (net (code "122") (name "unconnected-(IC1-PB4-Pad90)") (class "Default")
      (node (ref "IC1") (pin "90") (pinfunction "PB4_90") (pintype "passive"))
    )
    (net (code "123") (name "unconnected-(IC1-PB5-Pad91)") (class "Default")
      (node (ref "IC1") (pin "91") (pinfunction "PB5_91") (pintype "passive"))
    )
    (net (code "124") (name "unconnected-(IC1-PB6-Pad92)") (class "Default")
      (node (ref "IC1") (pin "92") (pinfunction "PB6_92") (pintype "passive"))
    )
    (net (code "125") (name "unconnected-(IC1-PB9-Pad96)") (class "Default")
      (node (ref "IC1") (pin "96") (pinfunction "PB9_96") (pintype "passive"))
    )
    (net (code "126") (name "unconnected-(IC1-PB14-Pad53)") (class "Default")
      (node (ref "IC1") (pin "53") (pinfunction "PB14_53") (pintype "passive"))
    )
    (net (code "127") (name "unconnected-(IC1-PB15-Pad54)") (class "Default")
      (node (ref "IC1") (pin "54") (pinfunction "PB15_54") (pintype "passive"))
    )
    (net (code "128") (name "unconnected-(IC1-PC0-Pad15)") (class "Default")
      (node (ref "IC1") (pin "15") (pinfunction "PC0_15") (pintype "passive"))
    )
    (net (code "129") (name "unconnected-(IC1-PC1-Pad16)") (class "Default")
      (node (ref "IC1") (pin "16") (pinfunction "PC1_16") (pintype "passive"))
    )
    (net (code "130") (name "unconnected-(IC1-PC2-Pad17)") (class "Default")
      (node (ref "IC1") (pin "17") (pinfunction "PC2_17") (pintype "passive"))
    )
    (net (code "131") (name "unconnected-(IC1-PC3-Pad18)") (class "Default")
      (node (ref "IC1") (pin "18") (pinfunction "PC3_18") (pintype "passive"))
    )
    (net (code "132") (name "unconnected-(IC1-PC4-Pad33)") (class "Default")
      (node (ref "IC1") (pin "33") (pinfunction "PC4_33") (pintype "passive"))
    )
    (net (code "133") (name "unconnected-(IC1-PC5-Pad34)") (class "Default")
      (node (ref "IC1") (pin "34") (pinfunction "PC5_34") (pintype "passive"))
    )
    (net (code "134") (name "unconnected-(IC1-PC6-Pad63)") (class "Default")
      (node (ref "IC1") (pin "63") (pinfunction "PC6_63") (pintype "passive"))
    )
    (net (code "135") (name "unconnected-(IC1-PC7-Pad64)") (class "Default")
      (node (ref "IC1") (pin "64") (pinfunction "PC7_64") (pintype "passive"))
    )
    (net (code "136") (name "unconnected-(IC1-PC8-Pad65)") (class "Default")
      (node (ref "IC1") (pin "65") (pinfunction "PC8_65") (pintype "passive"))
    )
    (net (code "137") (name "unconnected-(IC1-PC9-Pad66)") (class "Default")
      (node (ref "IC1") (pin "66") (pinfunction "PC9_66") (pintype "passive"))
    )
    (net (code "138") (name "unconnected-(IC1-PC10-Pad78)") (class "Default")
      (node (ref "IC1") (pin "78") (pinfunction "PC10_78") (pintype "passive"))
    )
    (net (code "139") (name "unconnected-(IC1-PC11-Pad79)") (class "Default")
      (node (ref "IC1") (pin "79") (pinfunction "PC11_79") (pintype "passive"))
    )
    (net (code "140") (name "unconnected-(IC1-PC12-Pad80)") (class "Default")
      (node (ref "IC1") (pin "80") (pinfunction "PC12_80") (pintype "passive"))
    )
    (net (code "141") (name "unconnected-(IC1-PD0-Pad81)") (class "Default")
      (node (ref "IC1") (pin "81") (pinfunction "PD0_81") (pintype "passive"))
    )
    (net (code "142") (name "unconnected-(IC1-PD1-Pad82)") (class "Default")
      (node (ref "IC1") (pin "82") (pinfunction "PD1_82") (pintype "passive"))
    )
    (net (code "143") (name "unconnected-(IC1-PD2-Pad83)") (class "Default")
      (node (ref "IC1") (pin "83") (pinfunction "PD2_83") (pintype "passive"))
    )
    (net (code "144") (name "unconnected-(IC1-PD3-Pad84)") (class "Default")
      (node (ref "IC1") (pin "84") (pinfunction "PD3_84") (pintype "passive"))
    )
    (net (code "145") (name "unconnected-(IC1-PD4-Pad85)") (class "Default")
      (node (ref "IC1") (pin "85") (pinfunction "PD4_85") (pintype "passive"))
    )
    (net (code "146") (name "unconnected-(IC1-PD7-Pad88)") (class "Default")
      (node (ref "IC1") (pin "88") (pinfunction "PD7_88") (pintype "passive"))
    )
    (net (code "147") (name "unconnected-(IC1-PD10-Pad57)") (class "Default")
      (node (ref "IC1") (pin "57") (pinfunction "PD10_57") (pintype "passive"))
    )
    (net (code "148") (name "unconnected-(IC1-PE0-Pad97)") (class "Default")
      (node (ref "IC1") (pin "97") (pinfunction "PE0_97") (pintype "passive"))
    )
    (net (code "149") (name "unconnected-(IC1-PE1-Pad98)") (class "Default")
      (node (ref "IC1") (pin "98") (pinfunction "PE1_98") (pintype "passive"))
    )
    (net (code "150") (name "unconnected-(IC1-PE2-Pad1)") (class "Default")
      (node (ref "IC1") (pin "1") (pinfunction "PE2_1") (pintype "passive"))
    )
    (net (code "151") (name "unconnected-(IC1-PE3-Pad2)") (class "Default")
      (node (ref "IC1") (pin "2") (pinfunction "PE3_2") (pintype "passive"))
    )
    (net (code "152") (name "unconnected-(IC1-PE4-Pad3)") (class "Default")
      (node (ref "IC1") (pin "3") (pinfunction "PE4_3") (pintype "passive"))
    )
    (net (code "153") (name "unconnected-(IC1-PE5-Pad4)") (class "Default")
      (node (ref "IC1") (pin "4") (pinfunction "PE5_4") (pintype "passive"))
    )
    (net (code "154") (name "unconnected-(IC1-PE6-Pad5)") (class "Default")
      (node (ref "IC1") (pin "5") (pinfunction "PE6_5") (pintype "passive"))
    )
    (net (code "155") (name "unconnected-(IC1-PE7-Pad38)") (class "Default")
      (node (ref "IC1") (pin "38") (pinfunction "PE7_38") (pintype "passive"))
    )
    (net (code "156") (name "unconnected-(IC1-PE8-Pad39)") (class "Default")
      (node (ref "IC1") (pin "39") (pinfunction "PE8_39") (pintype "passive"))
    )
    (net (code "157") (name "unconnected-(IC1-PE10-Pad41)") (class "Default")
      (node (ref "IC1") (pin "41") (pinfunction "PE10_41") (pintype "passive"))
    )
    (net (code "158") (name "unconnected-(IC1-PE12-Pad43)") (class "Default")
      (node (ref "IC1") (pin "43") (pinfunction "PE12_43") (pintype "passive"))
    )
    (net (code "159") (name "unconnected-(IC1-PE15-Pad46)") (class "Default")
      (node (ref "IC1") (pin "46") (pinfunction "PE15_46") (pintype "passive"))
    )
    (net (code "160") (name "unconnected-(IC5-VREF-Pad5)") (class "Default")
      (node (ref "IC5") (pin "5") (pinfunction "VREF_5") (pintype "passive+no_connect"))
    )
    (net (code "161") (name "unconnected-(IC6-VREF-Pad5)") (class "Default")
      (node (ref "IC6") (pin "5") (pinfunction "VREF_5") (pintype "passive+no_connect"))
    )
    (net (code "162") (name "unconnected-(IC7-NC-Pad1)") (class "Default")
      (node (ref "IC7") (pin "1") (pinfunction "NC_1") (pintype "passive+no_connect"))
    )
    (net (code "163") (name "unconnected-(IC8-NC-Pad1)") (class "Default")
      (node (ref "IC8") (pin "1") (pinfunction "NC_1") (pintype "passive+no_connect"))
    )
    (net (code "164") (name "unconnected-(IC9-NC-Pad1)") (class "Default")
      (node (ref "IC9") (pin "1") (pinfunction "NC_1") (pintype "passive+no_connect"))
    )
    (net (code "165") (name "unconnected-(J5-Pad5)") (class "Default")
      (node (ref "J5") (pin "5") (pinfunction "5_5") (pintype "passive+no_connect"))
    )
    (net (code "166") (name "unconnected-(J5-Pad6)") (class "Default")
      (node (ref "J5") (pin "6") (pinfunction "6_6") (pintype "passive+no_connect"))
    )
    (net (code "167") (name "unconnected-(J5-Pad7)") (class "Default")
      (node (ref "J5") (pin "7") (pinfunction "7_7") (pintype "passive+no_connect"))
    )
  )
)
